# PCB_-_BOARD.net
KiCad netlist of a schematic drawn in EAGLE
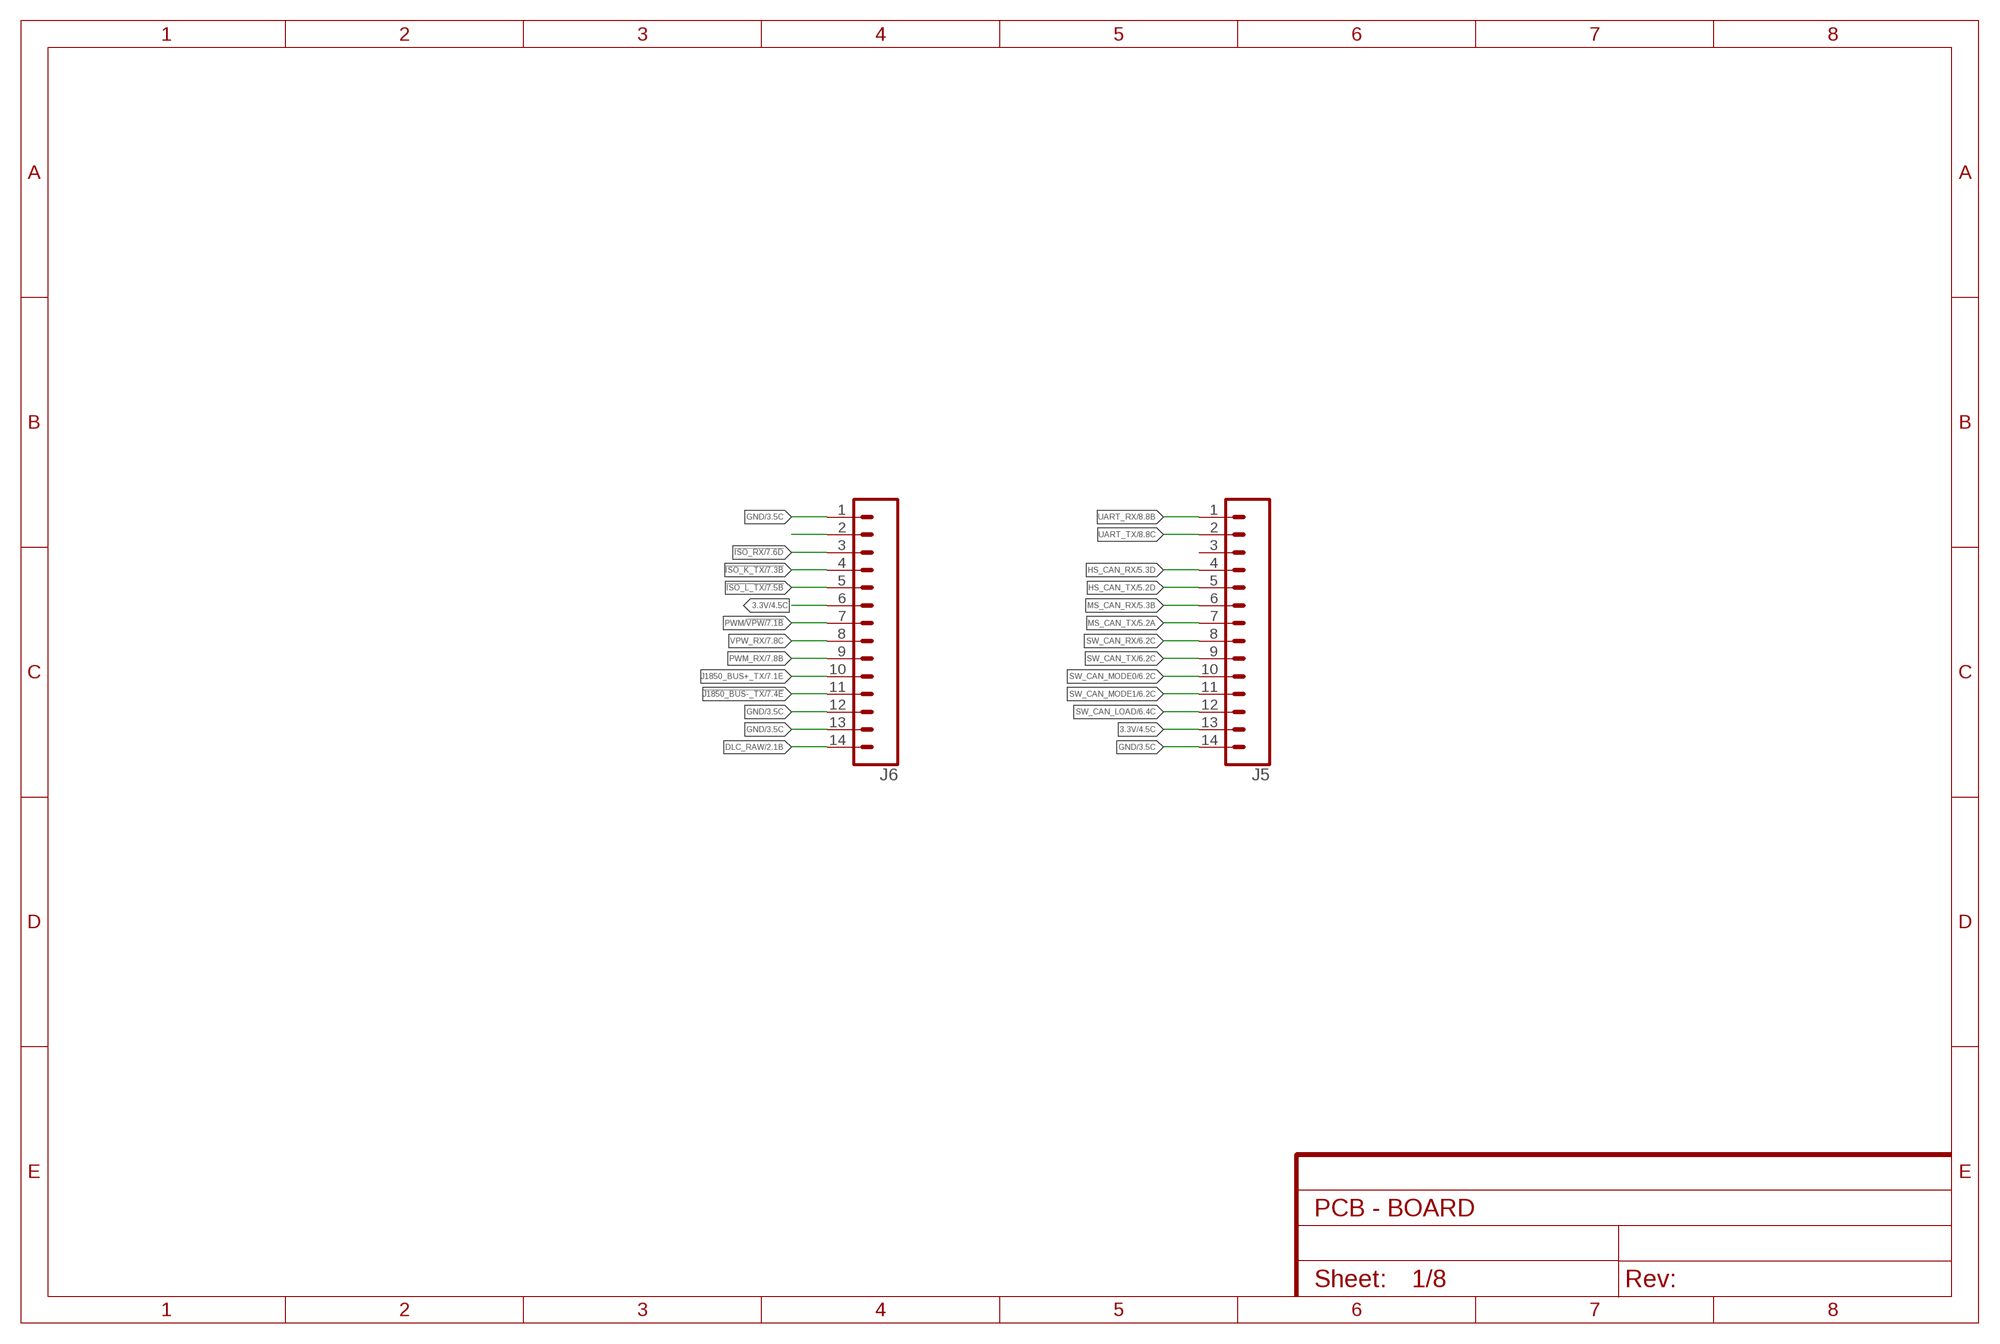
[diagram p0: schematic, sheet 1]
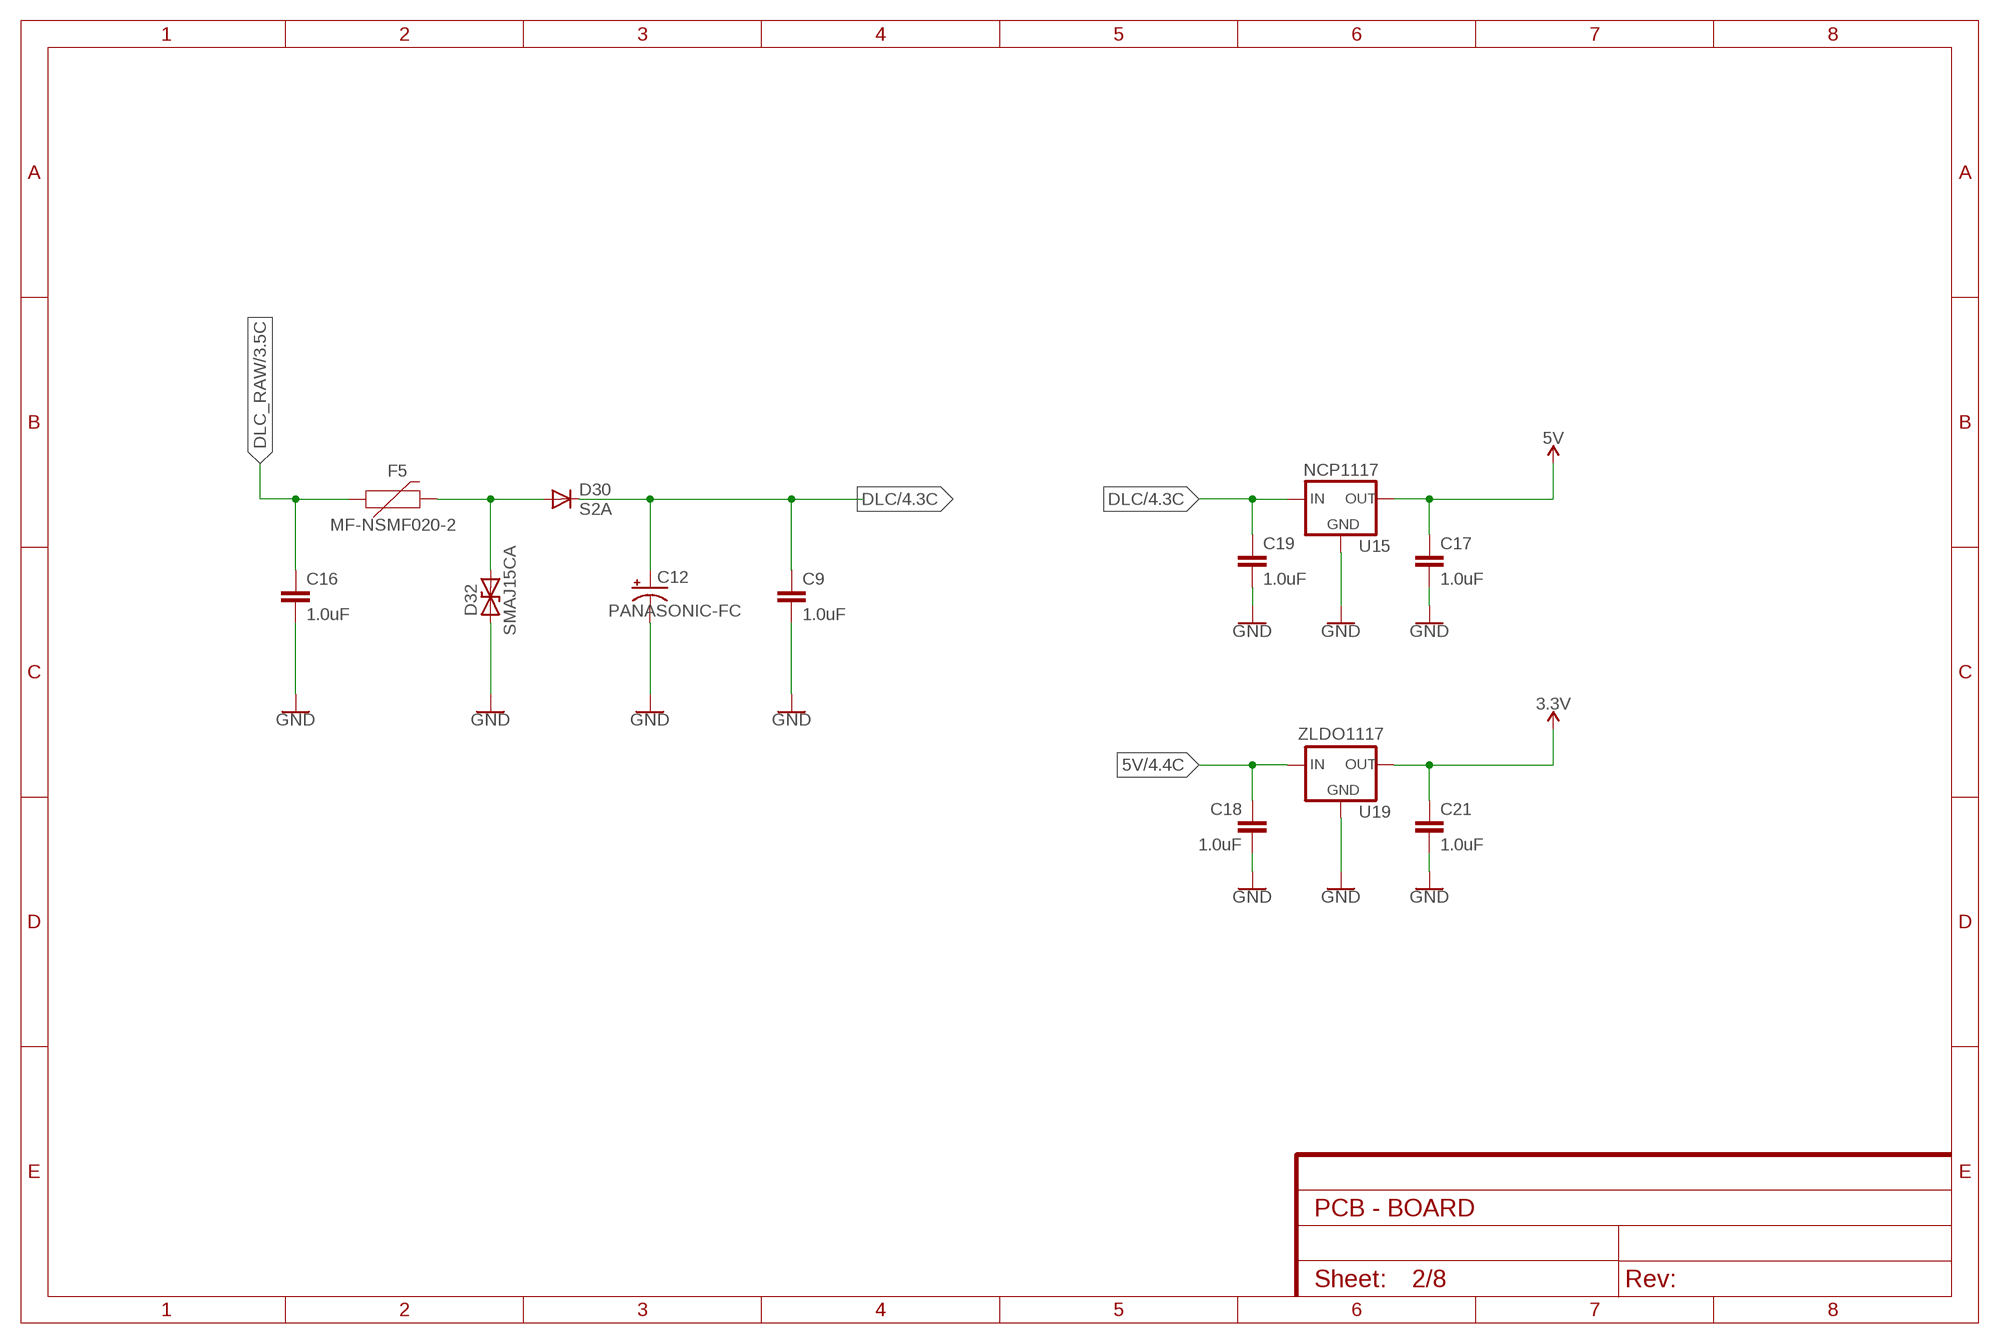
[diagram p1: schematic, sheet 2]
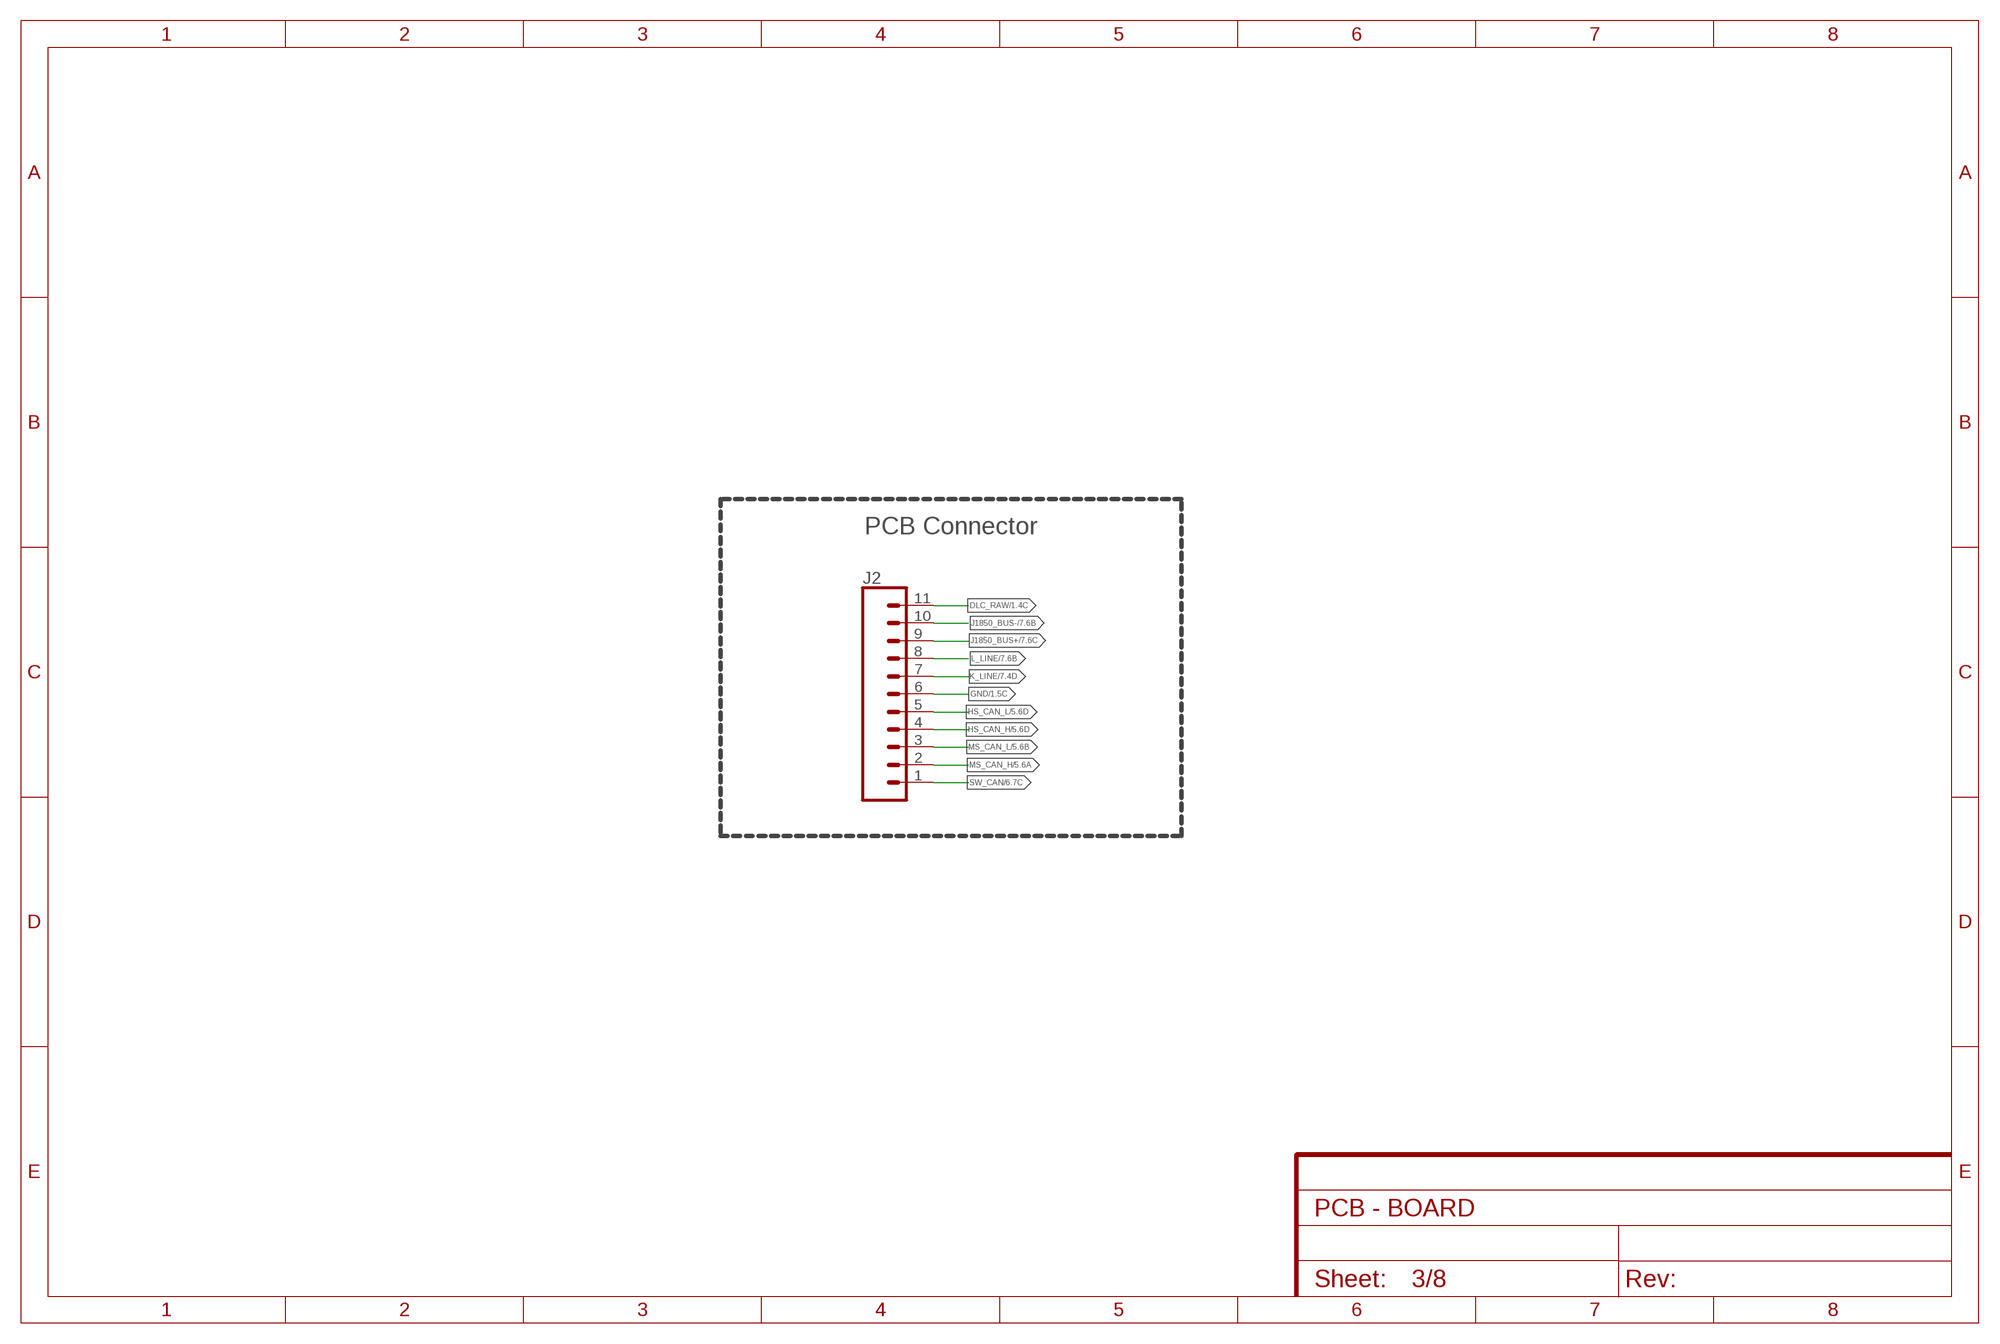
[diagram p2: schematic, sheet 3]
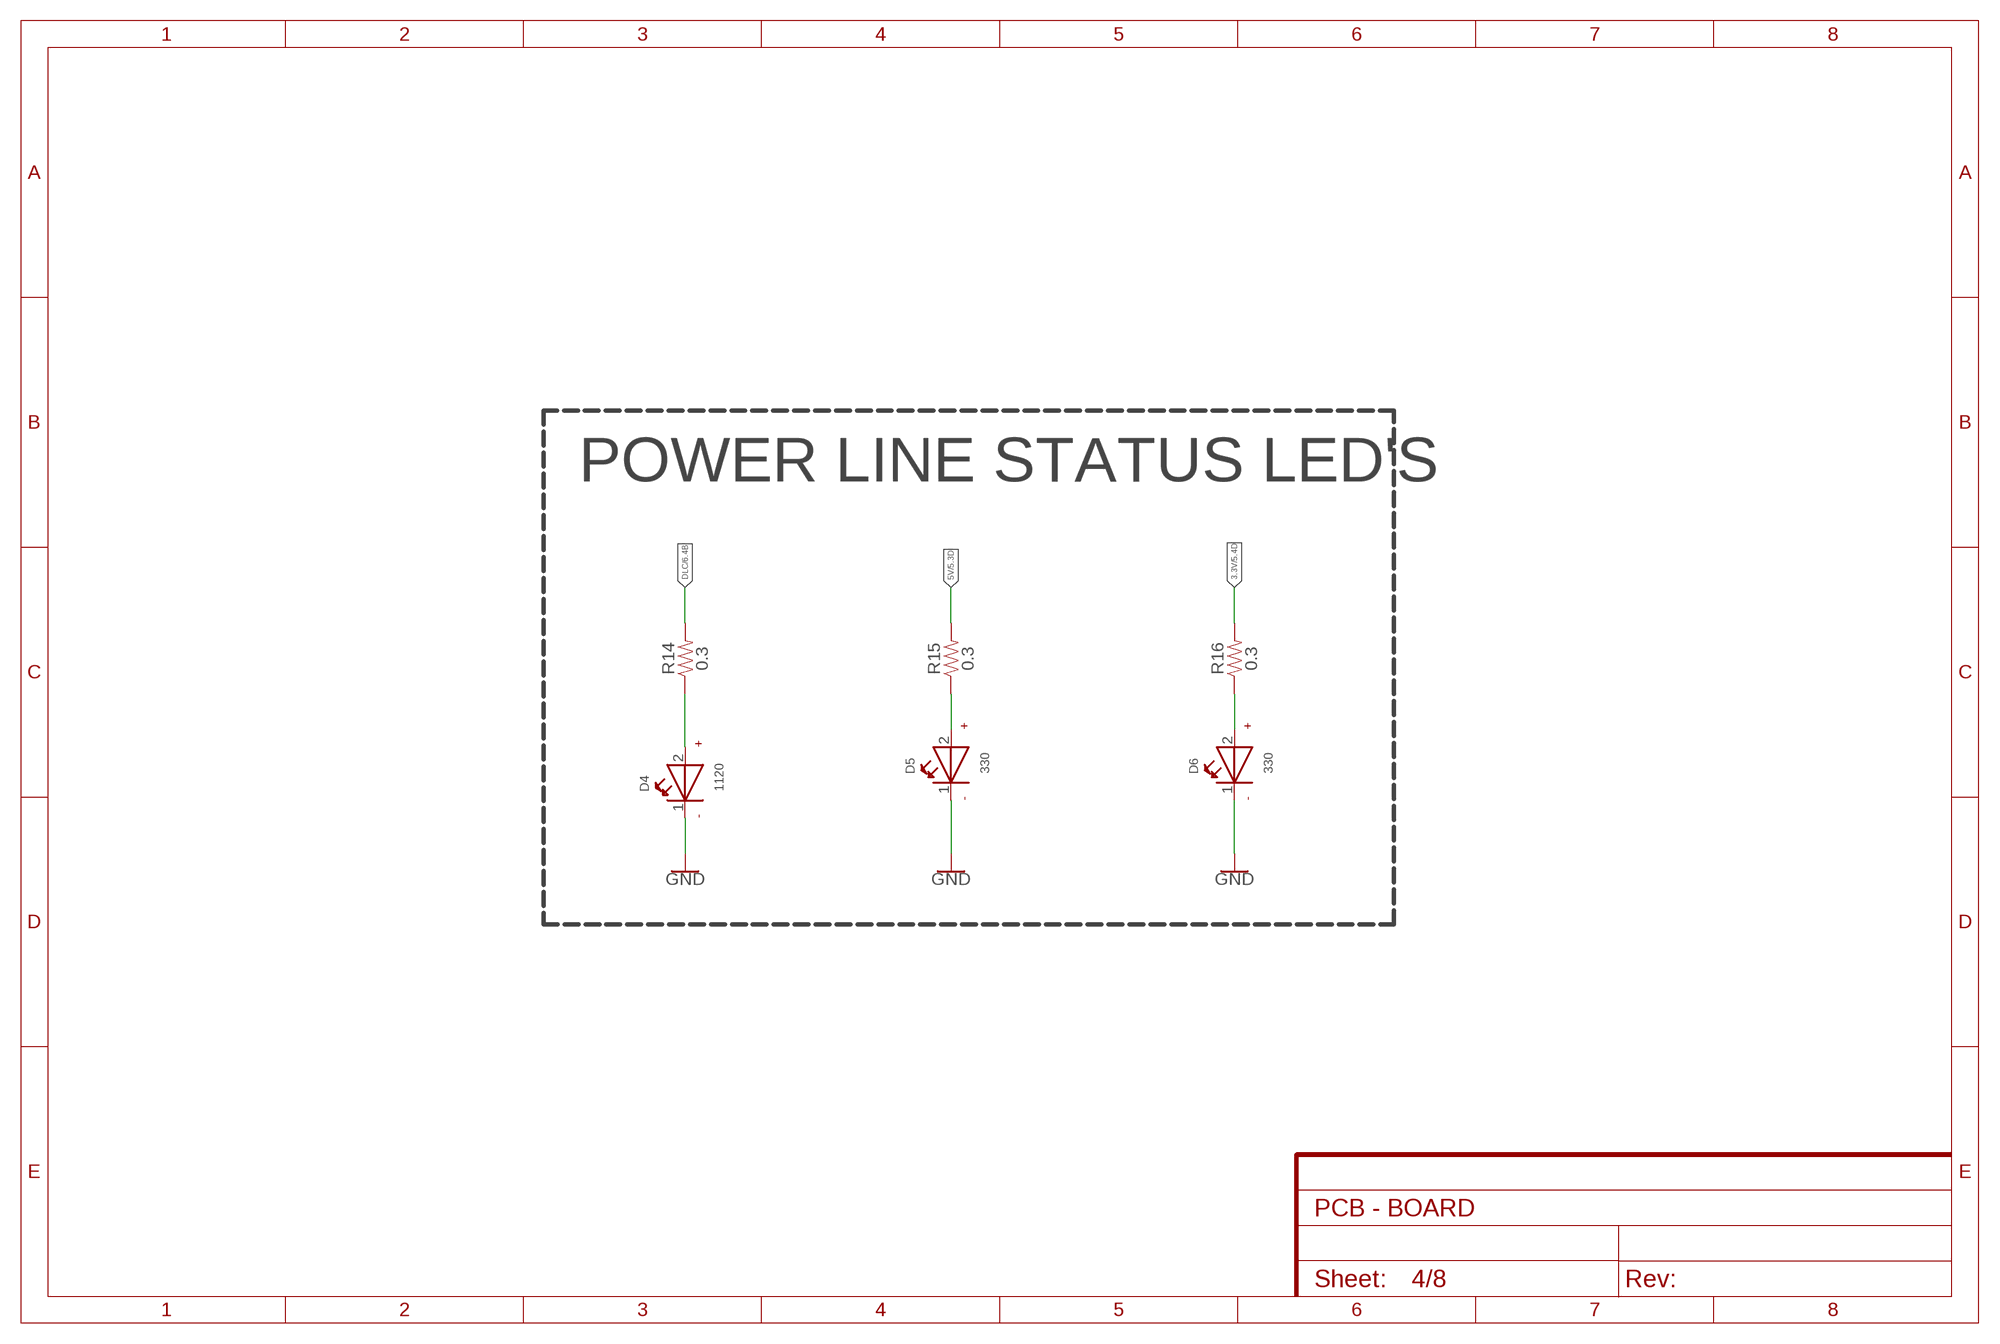
[diagram p3: schematic, sheet 4]
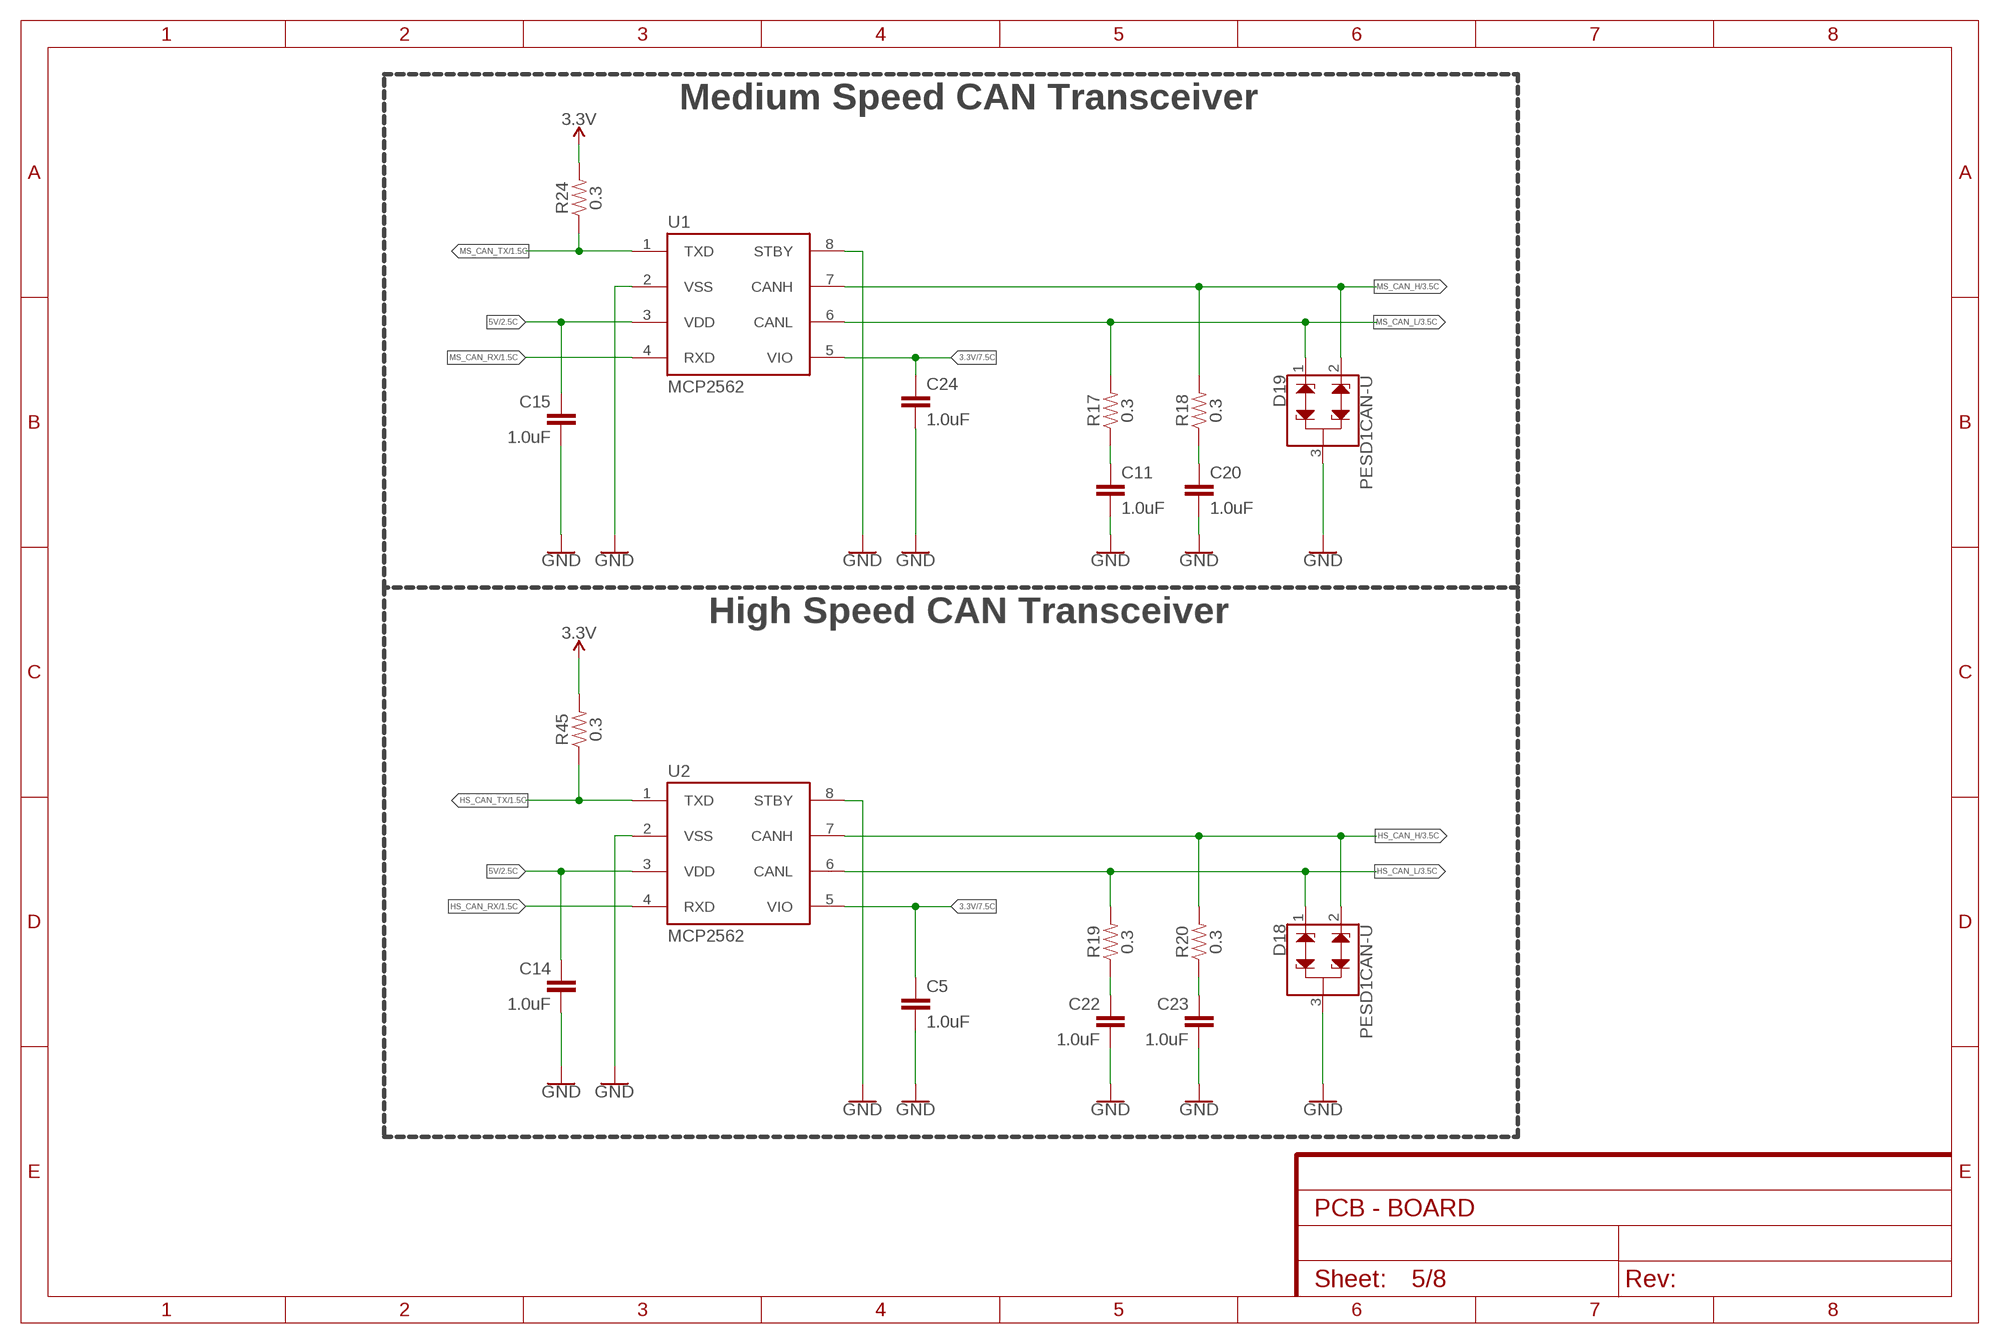
[diagram p4: schematic, sheet 5]
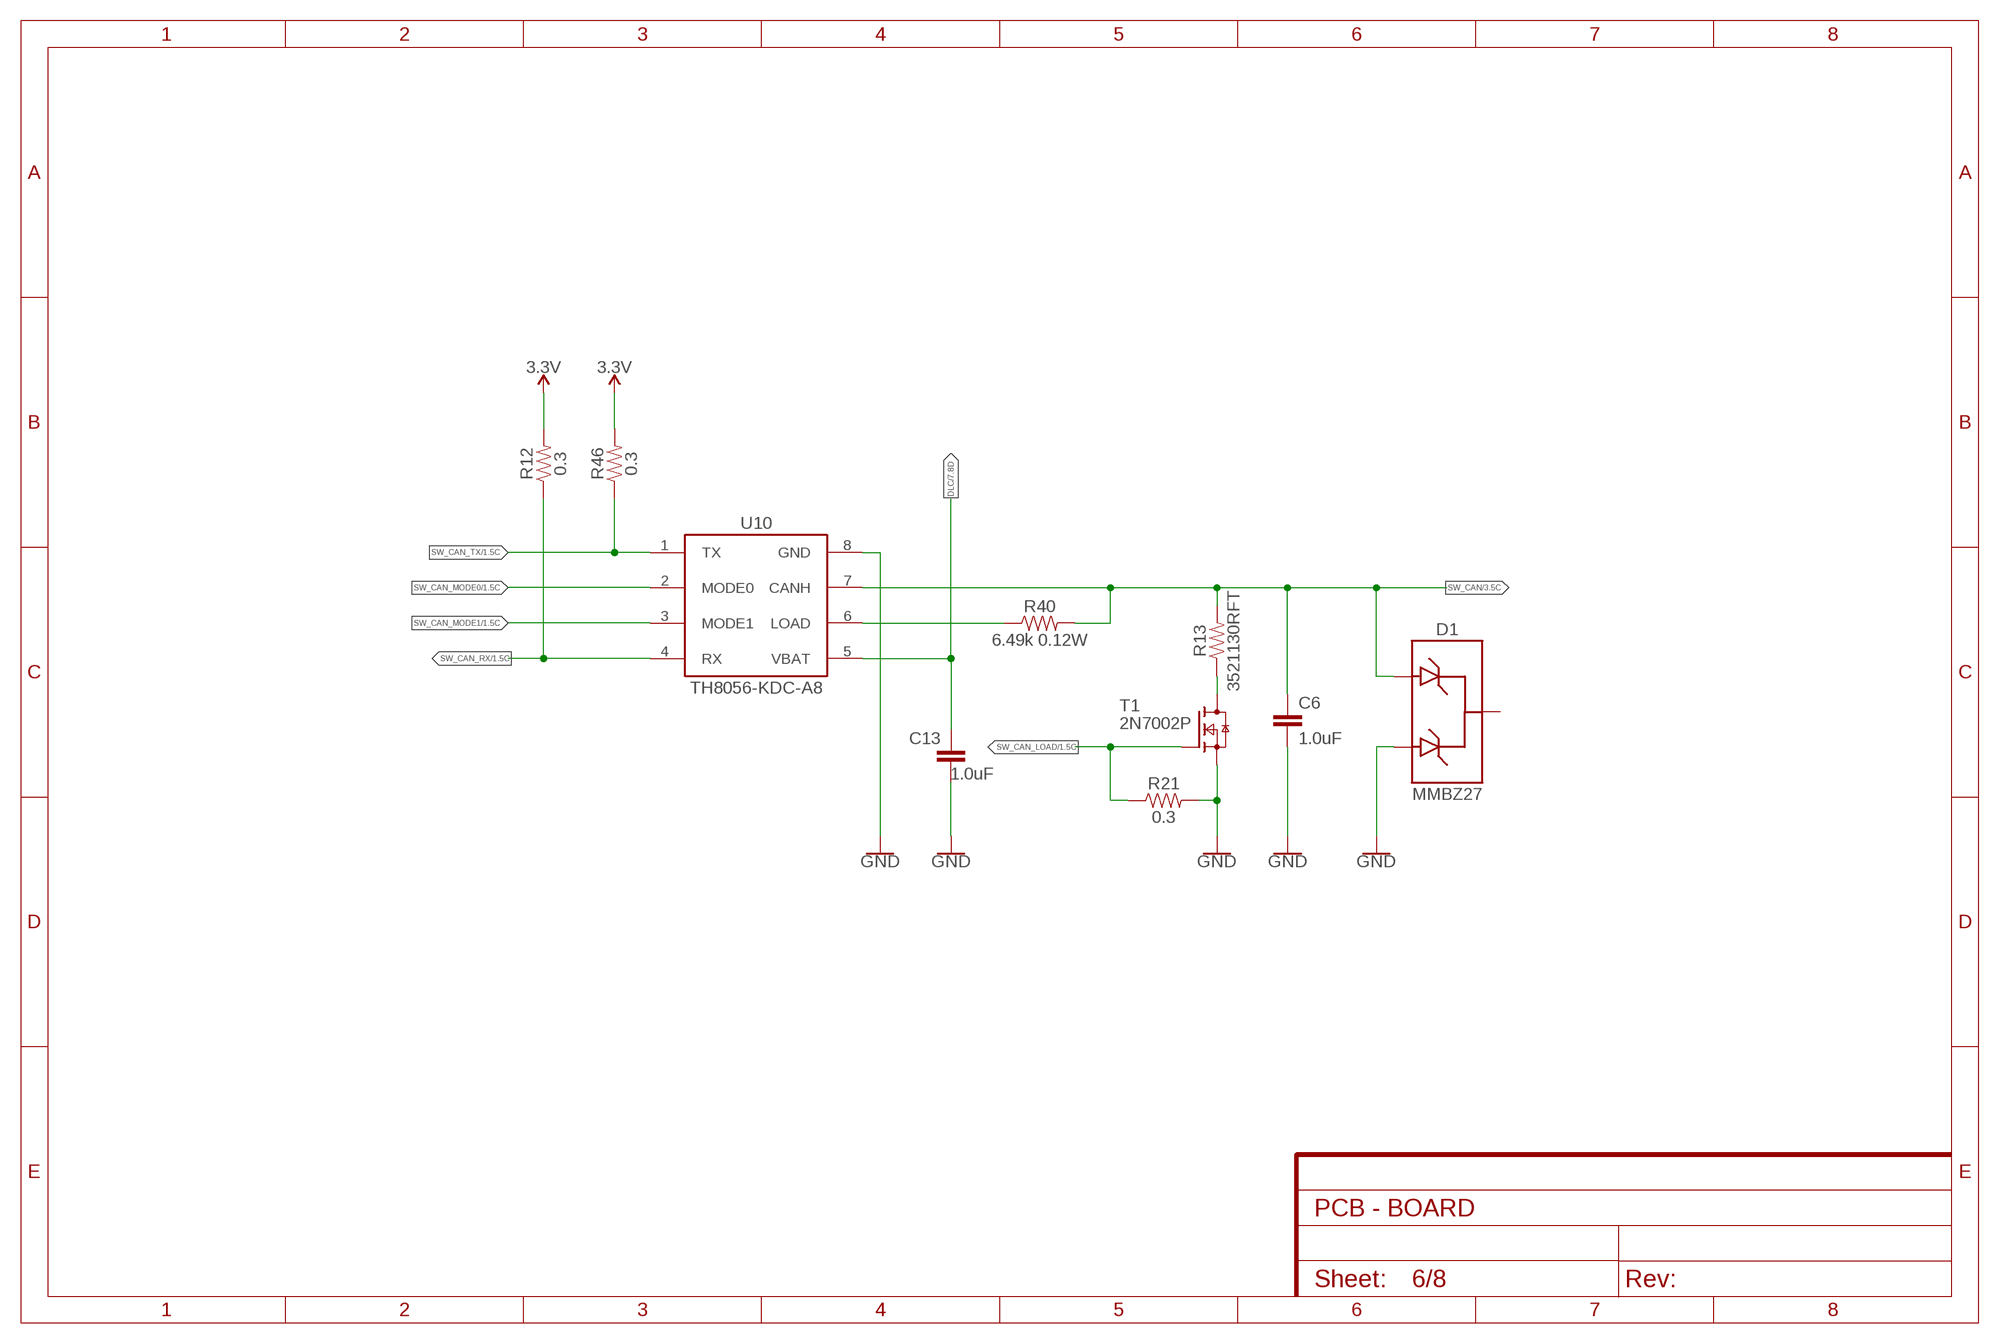
[diagram p5: schematic, sheet 6]
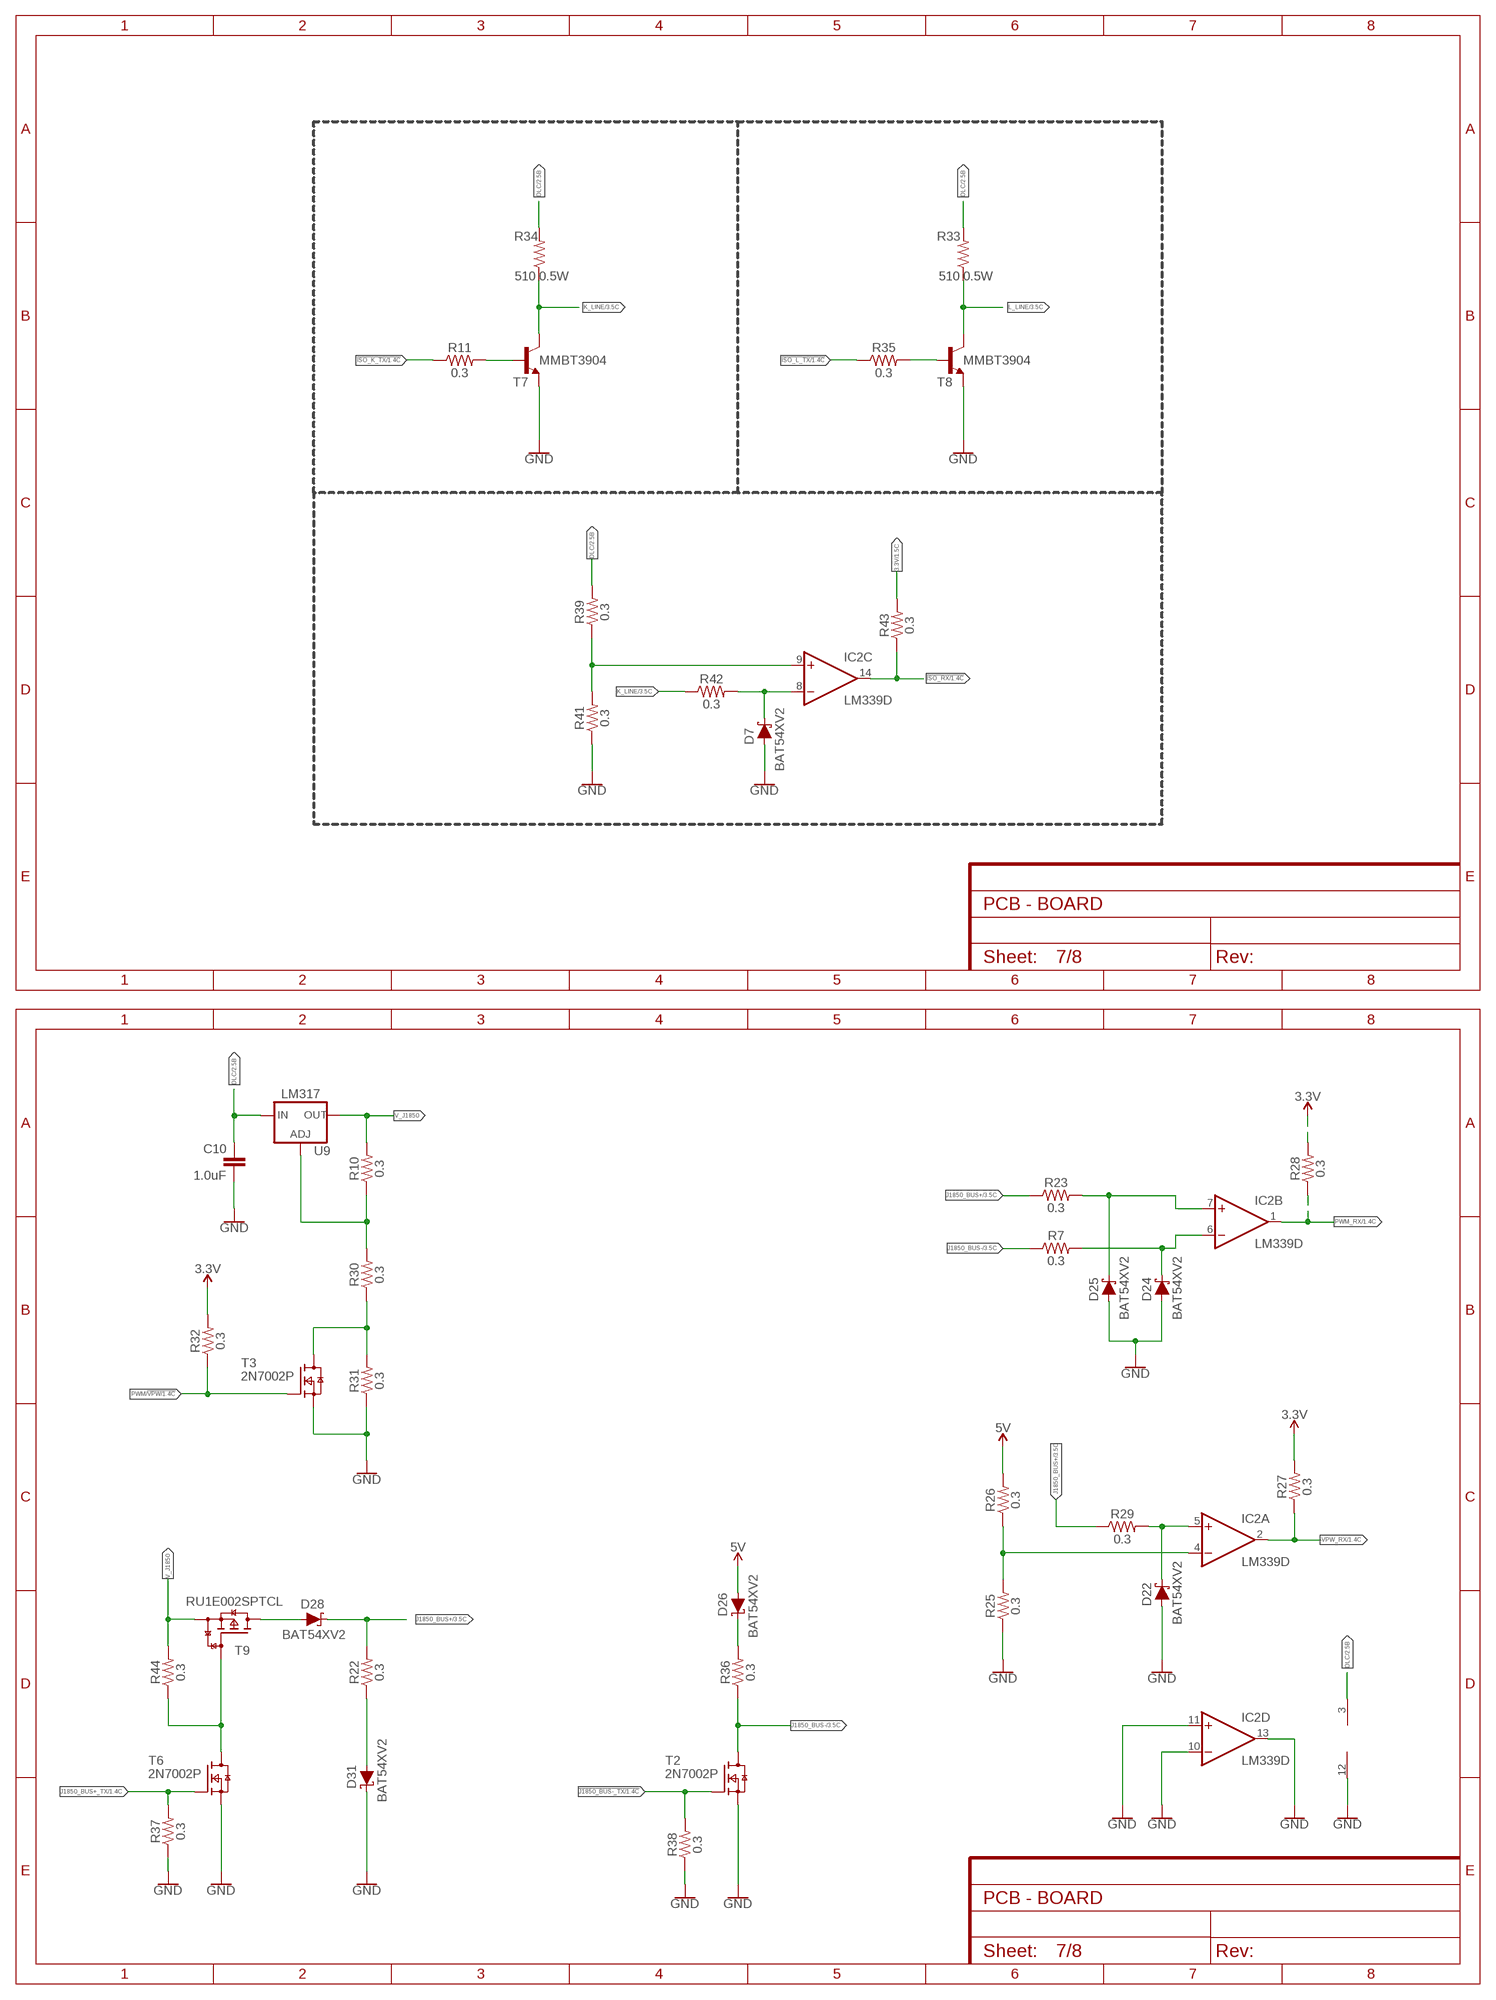
[diagram p6: schematic, sheet 7]
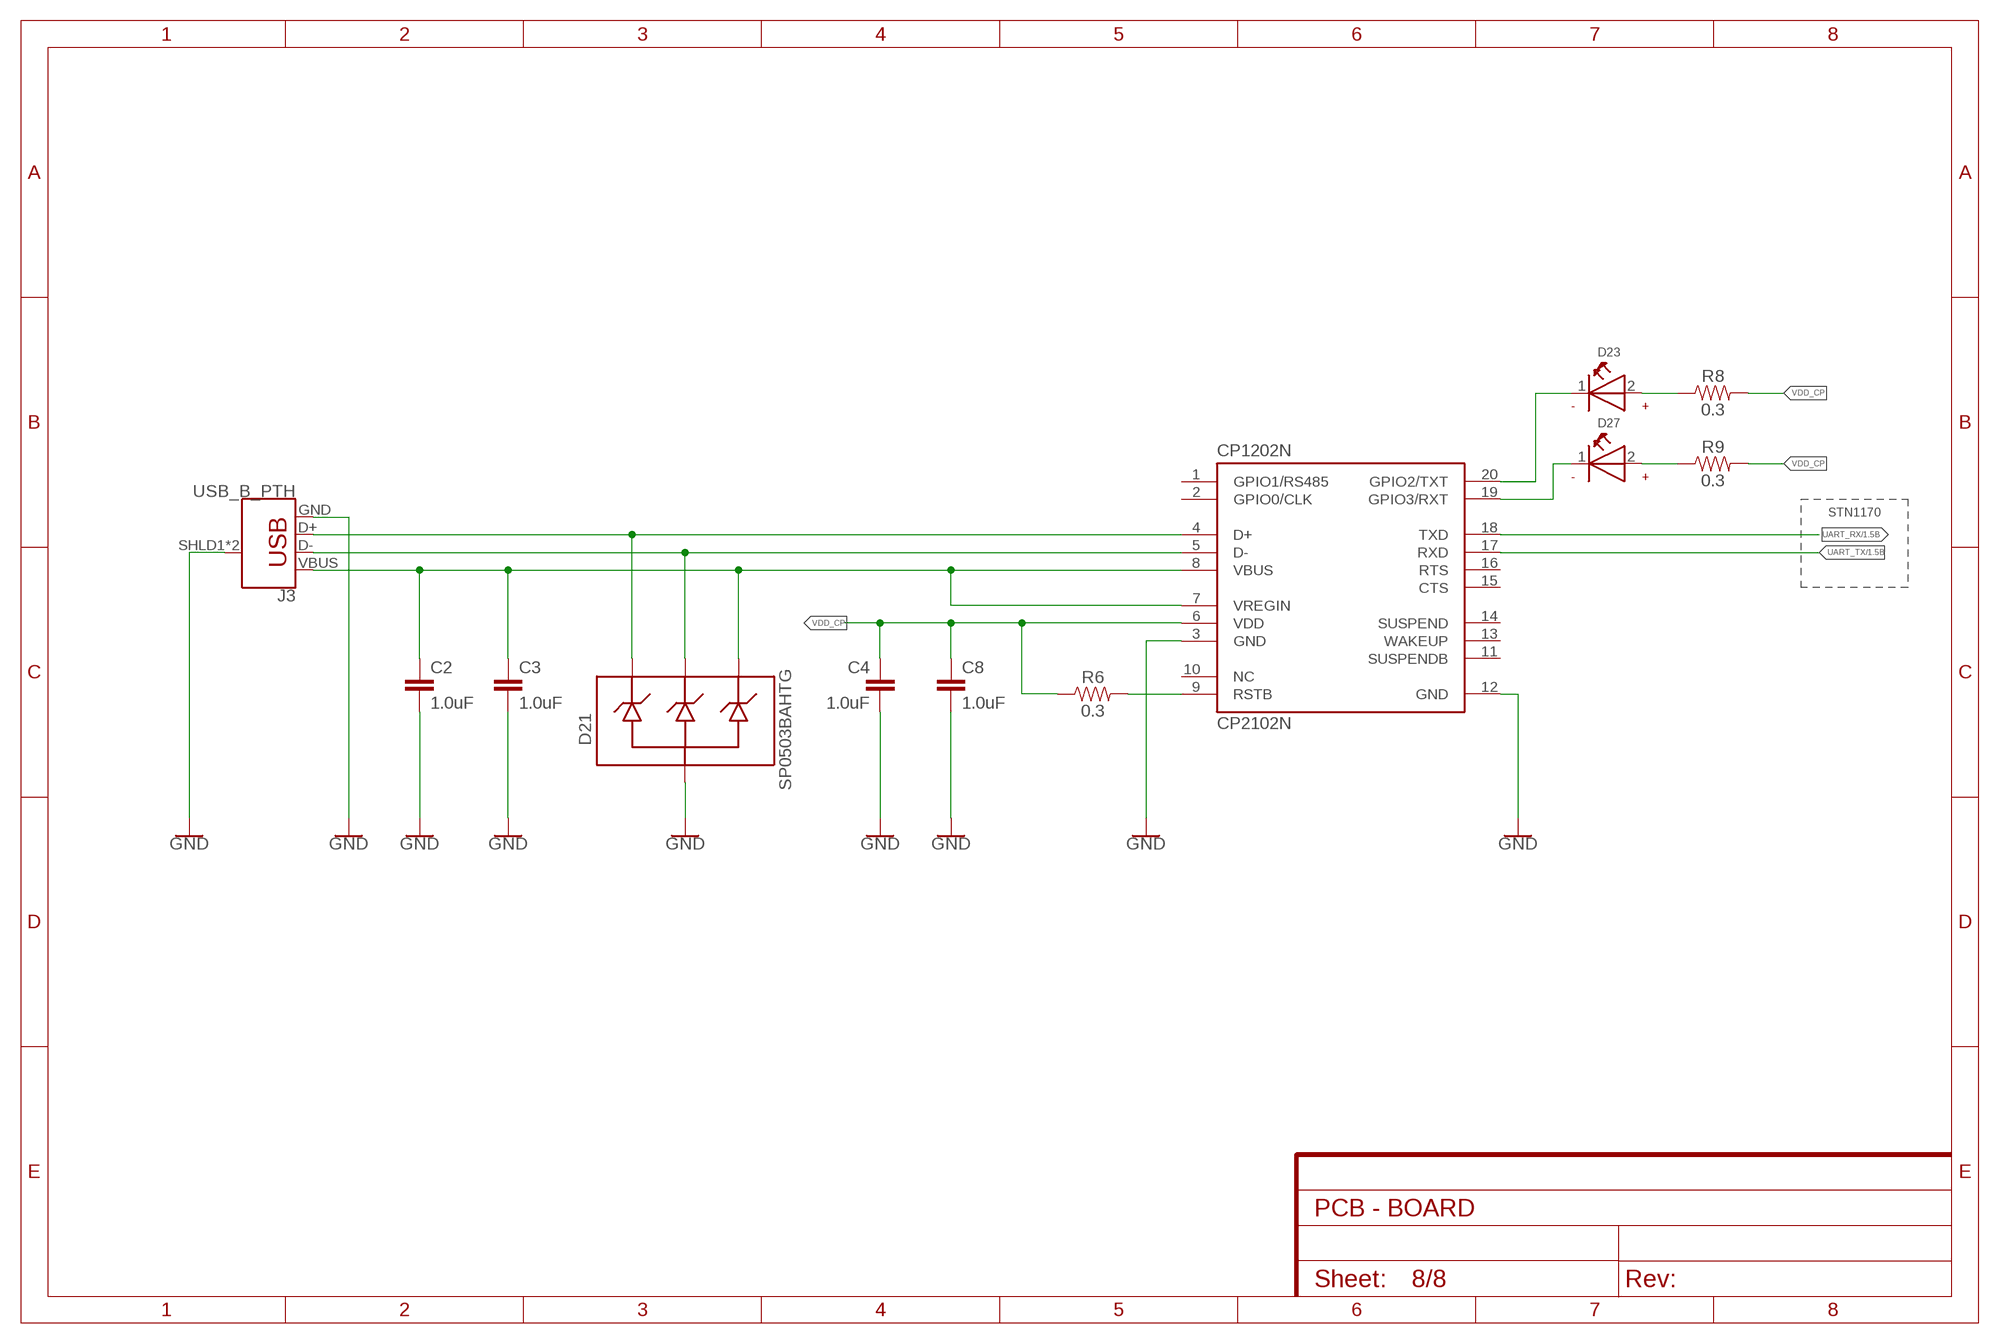
[diagram p7: schematic, sheet 8]

(export (version "E")
  (design (tool "Eeschema 10.0.6"))
  (components
    (comp (ref "C6")
      (value "1.0uF")
      (footprint "eagle-import:0805")
      (libsource (lib "eagle-import") (part "1.0UF-0805-25V-(+80/-20%)"))
    )
    (comp (ref "C13")
      (value "1.0uF")
      (footprint "eagle-import:0805")
      (libsource (lib "eagle-import") (part "1.0UF-0805-25V-(+80/-20%)"))
    )
    (comp (ref "D1")
      (value "MMBZ27")
      (footprint "eagle-import:SOT23-3")
      (libsource (lib "eagle-import") (part "MMBZ27"))
    )
    (comp (ref "R12")
      (value "0.3")
      (footprint "eagle-import:0805")
      (libsource (lib "eagle-import") (part "0.3OHM-0805-1/8W-1%"))
    )
    (comp (ref "R13")
      (value "3521130RFT")
      (footprint "eagle-import:3521")
      (libsource (lib "eagle-import") (part "3521130RFT"))
    )
    (comp (ref "R21")
      (value "0.3")
      (footprint "eagle-import:0805")
      (libsource (lib "eagle-import") (part "0.3OHM-0805-1/8W-1%"))
    )
    (comp (ref "R40")
      (value "6.49k 0.12W")
      (footprint "eagle-import:1206")
      (libsource (lib "eagle-import") (part "10OHM-1206-1/4W-1%"))
    )
    (comp (ref "R46")
      (value "0.3")
      (footprint "eagle-import:0805")
      (libsource (lib "eagle-import") (part "0.3OHM-0805-1/8W-1%"))
    )
    (comp (ref "T1")
      (value "2N7002P")
      (footprint "eagle-import:SOT23")
      (libsource (lib "eagle-import") (part "2N7002P"))
    )
    (comp (ref "U10")
      (value "TH8056-KDC-A8")
      (footprint "eagle-import:SOIC-8")
      (libsource (lib "eagle-import") (part "TH8056-KDC-A8"))
    )
    (comp (ref "J5")
      (value "CONN_14")
      (footprint "eagle-import:1X14")
      (libsource (lib "eagle-import") (part "CONN_14"))
    )
    (comp (ref "J6")
      (value "CONN_14")
      (footprint "eagle-import:1X14")
      (libsource (lib "eagle-import") (part "CONN_14"))
    )
    (comp (ref "D4")
      (value "1120")
      (footprint "eagle-import:WL-SMCW_1206")
      (libsource (lib "eagle-import") (part "WL-SMCW-150120BS75000-B"))
    )
    (comp (ref "D5")
      (value "330")
      (footprint "eagle-import:WL-SMCW_1206")
      (libsource (lib "eagle-import") (part "WL-SMCW-150120BS75000-B"))
    )
    (comp (ref "D6")
      (value "330")
      (footprint "eagle-import:WL-SMCW_1206")
      (libsource (lib "eagle-import") (part "WL-SMCW-150120BS75000-B"))
    )
    (comp (ref "R14")
      (value "0.3")
      (footprint "eagle-import:0805")
      (libsource (lib "eagle-import") (part "0.3OHM-0805-1/8W-1%"))
    )
    (comp (ref "R15")
      (value "0.3")
      (footprint "eagle-import:0805")
      (libsource (lib "eagle-import") (part "0.3OHM-0805-1/8W-1%"))
    )
    (comp (ref "R16")
      (value "0.3")
      (footprint "eagle-import:0805")
      (libsource (lib "eagle-import") (part "0.3OHM-0805-1/8W-1%"))
    )
    (comp (ref "C10")
      (value "1.0uF")
      (footprint "eagle-import:0805")
      (libsource (lib "eagle-import") (part "1.0UF-0805-25V-(+80/-20%)"))
    )
    (comp (ref "D7")
      (value "BAT54XV2")
      (footprint "eagle-import:SOD-523F")
      (libsource (lib "eagle-import") (part "BAT54XV2"))
    )
    (comp (ref "D22")
      (value "BAT54XV2")
      (footprint "eagle-import:SOD-523F")
      (libsource (lib "eagle-import") (part "BAT54XV2"))
    )
    (comp (ref "D24")
      (value "BAT54XV2")
      (footprint "eagle-import:SOD-523F")
      (libsource (lib "eagle-import") (part "BAT54XV2"))
    )
    (comp (ref "D25")
      (value "BAT54XV2")
      (footprint "eagle-import:SOD-523F")
      (libsource (lib "eagle-import") (part "BAT54XV2"))
    )
    (comp (ref "D26")
      (value "BAT54XV2")
      (footprint "eagle-import:SOD-523F")
      (libsource (lib "eagle-import") (part "BAT54XV2"))
    )
    (comp (ref "D28")
      (value "BAT54XV2")
      (footprint "eagle-import:SOD-523F")
      (libsource (lib "eagle-import") (part "BAT54XV2"))
    )
    (comp (ref "D31")
      (value "BAT54XV2")
      (footprint "eagle-import:SOD-523F")
      (libsource (lib "eagle-import") (part "BAT54XV2"))
    )
    (comp (ref "IC2")
      (value "LM339D")
      (footprint "eagle-import:SO14")
      (libsource (lib "eagle-import") (part "LM339D"))
    )
    (comp (ref "R7")
      (value "0.3")
      (footprint "eagle-import:0805")
      (libsource (lib "eagle-import") (part "0.3OHM-0805-1/8W-1%"))
    )
    (comp (ref "R10")
      (value "0.3")
      (footprint "eagle-import:0805")
      (libsource (lib "eagle-import") (part "0.3OHM-0805-1/8W-1%"))
    )
    (comp (ref "R11")
      (value "0.3")
      (footprint "eagle-import:0805")
      (libsource (lib "eagle-import") (part "0.3OHM-0805-1/8W-1%"))
    )
    (comp (ref "R22")
      (value "0.3")
      (footprint "eagle-import:0805")
      (libsource (lib "eagle-import") (part "0.3OHM-0805-1/8W-1%"))
    )
    (comp (ref "R23")
      (value "0.3")
      (footprint "eagle-import:0805")
      (libsource (lib "eagle-import") (part "0.3OHM-0805-1/8W-1%"))
    )
    (comp (ref "R25")
      (value "0.3")
      (footprint "eagle-import:0805")
      (libsource (lib "eagle-import") (part "0.3OHM-0805-1/8W-1%"))
    )
    (comp (ref "R26")
      (value "0.3")
      (footprint "eagle-import:0805")
      (libsource (lib "eagle-import") (part "0.3OHM-0805-1/8W-1%"))
    )
    (comp (ref "R27")
      (value "0.3")
      (footprint "eagle-import:0805")
      (libsource (lib "eagle-import") (part "0.3OHM-0805-1/8W-1%"))
    )
    (comp (ref "R28")
      (value "0.3")
      (footprint "eagle-import:0805")
      (libsource (lib "eagle-import") (part "0.3OHM-0805-1/8W-1%"))
    )
    (comp (ref "R29")
      (value "0.3")
      (footprint "eagle-import:0805")
      (libsource (lib "eagle-import") (part "0.3OHM-0805-1/8W-1%"))
    )
    (comp (ref "R30")
      (value "0.3")
      (footprint "eagle-import:0805")
      (libsource (lib "eagle-import") (part "0.3OHM-0805-1/8W-1%"))
    )
    (comp (ref "R31")
      (value "0.3")
      (footprint "eagle-import:0805")
      (libsource (lib "eagle-import") (part "0.3OHM-0805-1/8W-1%"))
    )
    (comp (ref "R32")
      (value "0.3")
      (footprint "eagle-import:0805")
      (libsource (lib "eagle-import") (part "0.3OHM-0805-1/8W-1%"))
    )
    (comp (ref "R33")
      (value "510 0.5W")
      (footprint "eagle-import:1210")
      (libsource (lib "eagle-import") (part "0.1OHM-1210-1/2W-1%"))
    )
    (comp (ref "R34")
      (value "510 0.5W")
      (footprint "eagle-import:1210")
      (libsource (lib "eagle-import") (part "0.1OHM-1210-1/2W-1%"))
    )
    (comp (ref "R35")
      (value "0.3")
      (footprint "eagle-import:0805")
      (libsource (lib "eagle-import") (part "0.3OHM-0805-1/8W-1%"))
    )
    (comp (ref "R36")
      (value "0.3")
      (footprint "eagle-import:0805")
      (libsource (lib "eagle-import") (part "0.3OHM-0805-1/8W-1%"))
    )
    (comp (ref "R37")
      (value "0.3")
      (footprint "eagle-import:0805")
      (libsource (lib "eagle-import") (part "0.3OHM-0805-1/8W-1%"))
    )
    (comp (ref "R38")
      (value "0.3")
      (footprint "eagle-import:0805")
      (libsource (lib "eagle-import") (part "0.3OHM-0805-1/8W-1%"))
    )
    (comp (ref "R39")
      (value "0.3")
      (footprint "eagle-import:0805")
      (libsource (lib "eagle-import") (part "0.3OHM-0805-1/8W-1%"))
    )
    (comp (ref "R41")
      (value "0.3")
      (footprint "eagle-import:0805")
      (libsource (lib "eagle-import") (part "0.3OHM-0805-1/8W-1%"))
    )
    (comp (ref "R42")
      (value "0.3")
      (footprint "eagle-import:0805")
      (libsource (lib "eagle-import") (part "0.3OHM-0805-1/8W-1%"))
    )
    (comp (ref "R43")
      (value "0.3")
      (footprint "eagle-import:0805")
      (libsource (lib "eagle-import") (part "0.3OHM-0805-1/8W-1%"))
    )
    (comp (ref "R44")
      (value "0.3")
      (footprint "eagle-import:0805")
      (libsource (lib "eagle-import") (part "0.3OHM-0805-1/8W-1%"))
    )
    (comp (ref "T2")
      (value "2N7002P")
      (footprint "eagle-import:SOT23")
      (libsource (lib "eagle-import") (part "2N7002P"))
    )
    (comp (ref "T3")
      (value "2N7002P")
      (footprint "eagle-import:SOT23")
      (libsource (lib "eagle-import") (part "2N7002P"))
    )
    (comp (ref "T6")
      (value "2N7002P")
      (footprint "eagle-import:SOT23")
      (libsource (lib "eagle-import") (part "2N7002P"))
    )
    (comp (ref "T7")
      (value "MMBT3904")
      (footprint "eagle-import:SOT23-BEC")
      (libsource (lib "eagle-import") (part "-NPN-SOT23-BECMMBT3904LT1"))
    )
    (comp (ref "T8")
      (value "MMBT3904")
      (footprint "eagle-import:SOT23-BEC")
      (libsource (lib "eagle-import") (part "-NPN-SOT23-BECMMBT3904LT1"))
    )
    (comp (ref "T9")
      (value "RU1E002SPTCL")
      (footprint "eagle-import:SOT323")
      (libsource (lib "eagle-import") (part "BSS84AKW"))
    )
    (comp (ref "U9")
      (value "LM317")
      (footprint "eagle-import:SOT223")
      (libsource (lib "eagle-import") (part "V_REG_317SMD"))
    )
    (comp (ref "C9")
      (value "1.0uF")
      (footprint "eagle-import:0805")
      (libsource (lib "eagle-import") (part "1.0UF-0805-25V-(+80/-20%)"))
    )
    (comp (ref "C12")
      (value "PANASONIC-FC")
      (footprint "eagle-import:5X11")
      (libsource (lib "eagle-import") (part "PANASONIC-FC"))
    )
    (comp (ref "C16")
      (value "1.0uF")
      (footprint "eagle-import:0805")
      (libsource (lib "eagle-import") (part "1.0UF-0805-25V-(+80/-20%)"))
    )
    (comp (ref "C17")
      (value "1.0uF")
      (footprint "eagle-import:0805")
      (libsource (lib "eagle-import") (part "1.0UF-0805-25V-(+80/-20%)"))
    )
    (comp (ref "C18")
      (value "1.0uF")
      (footprint "eagle-import:0805")
      (libsource (lib "eagle-import") (part "1.0UF-0805-25V-(+80/-20%)"))
    )
    (comp (ref "C19")
      (value "1.0uF")
      (footprint "eagle-import:0805")
      (libsource (lib "eagle-import") (part "1.0UF-0805-25V-(+80/-20%)"))
    )
    (comp (ref "C21")
      (value "1.0uF")
      (footprint "eagle-import:0805")
      (libsource (lib "eagle-import") (part "1.0UF-0805-25V-(+80/-20%)"))
    )
    (comp (ref "D30")
      (value "S2A")
      (footprint "eagle-import:DO214AA")
      (fields (field (name "MF") "Fairchild"))
      (libsource (lib "eagle-import") (part "S2A"))
    )
    (comp (ref "D32")
      (value "SMAJ15CA")
      (footprint "eagle-import:DO214AC")
      (fields (field (name "MF") "Littelfuse"))
      (libsource (lib "eagle-import") (part "SMAJCA15"))
    )
    (comp (ref "F5")
      (value "MF-NSMF020-2")
      (footprint "eagle-import:1206")
      (libsource (lib "eagle-import") (part "PPTC_THREE-QUARTER-AMP"))
    )
    (comp (ref "U15")
      (value "NCP1117")
      (footprint "eagle-import:TO-252")
      (libsource (lib "eagle-import") (part "NCP1117DPAK"))
    )
    (comp (ref "U19")
      (value "ZLDO1117")
      (footprint "eagle-import:SOT223")
      (libsource (lib "eagle-import") (part "ZLDO1117SOT223"))
    )
    (comp (ref "C5")
      (value "1.0uF")
      (footprint "eagle-import:0805")
      (libsource (lib "eagle-import") (part "1.0UF-0805-25V-(+80/-20%)"))
    )
    (comp (ref "C11")
      (value "1.0uF")
      (footprint "eagle-import:0805")
      (libsource (lib "eagle-import") (part "1.0UF-0805-25V-(+80/-20%)"))
    )
    (comp (ref "C14")
      (value "1.0uF")
      (footprint "eagle-import:0805")
      (libsource (lib "eagle-import") (part "1.0UF-0805-25V-(+80/-20%)"))
    )
    (comp (ref "C15")
      (value "1.0uF")
      (footprint "eagle-import:0805")
      (libsource (lib "eagle-import") (part "1.0UF-0805-25V-(+80/-20%)"))
    )
    (comp (ref "C20")
      (value "1.0uF")
      (footprint "eagle-import:0805")
      (libsource (lib "eagle-import") (part "1.0UF-0805-25V-(+80/-20%)"))
    )
    (comp (ref "C22")
      (value "1.0uF")
      (footprint "eagle-import:0805")
      (libsource (lib "eagle-import") (part "1.0UF-0805-25V-(+80/-20%)"))
    )
    (comp (ref "C23")
      (value "1.0uF")
      (footprint "eagle-import:0805")
      (libsource (lib "eagle-import") (part "1.0UF-0805-25V-(+80/-20%)"))
    )
    (comp (ref "C24")
      (value "1.0uF")
      (footprint "eagle-import:0805")
      (libsource (lib "eagle-import") (part "1.0UF-0805-25V-(+80/-20%)"))
    )
    (comp (ref "D18")
      (value "PESD1CAN-U")
      (footprint "eagle-import:SOT323")
      (libsource (lib "eagle-import") (part "PESD1CAN-U"))
    )
    (comp (ref "D19")
      (value "PESD1CAN-U")
      (footprint "eagle-import:SOT323")
      (libsource (lib "eagle-import") (part "PESD1CAN-U"))
    )
    (comp (ref "R17")
      (value "0.3")
      (footprint "eagle-import:0805")
      (libsource (lib "eagle-import") (part "0.3OHM-0805-1/8W-1%"))
    )
    (comp (ref "R18")
      (value "0.3")
      (footprint "eagle-import:0805")
      (libsource (lib "eagle-import") (part "0.3OHM-0805-1/8W-1%"))
    )
    (comp (ref "R19")
      (value "0.3")
      (footprint "eagle-import:0805")
      (libsource (lib "eagle-import") (part "0.3OHM-0805-1/8W-1%"))
    )
    (comp (ref "R20")
      (value "0.3")
      (footprint "eagle-import:0805")
      (libsource (lib "eagle-import") (part "0.3OHM-0805-1/8W-1%"))
    )
    (comp (ref "R24")
      (value "0.3")
      (footprint "eagle-import:0805")
      (libsource (lib "eagle-import") (part "0.3OHM-0805-1/8W-1%"))
    )
    (comp (ref "R45")
      (value "0.3")
      (footprint "eagle-import:0805")
      (libsource (lib "eagle-import") (part "0.3OHM-0805-1/8W-1%"))
    )
    (comp (ref "U1")
      (value "MCP2562")
      (footprint "eagle-import:SOIC-8")
      (libsource (lib "eagle-import") (part "MCP2562"))
    )
    (comp (ref "U2")
      (value "MCP2562")
      (footprint "eagle-import:SOIC-8")
      (libsource (lib "eagle-import") (part "MCP2562"))
    )
    (comp (ref "J2")
      (value "CONN_11")
      (footprint "eagle-import:1X11")
      (libsource (lib "eagle-import") (part "CONN_11"))
    )
    (comp (ref "C2")
      (value "1.0uF")
      (footprint "eagle-import:0805")
      (libsource (lib "eagle-import") (part "1.0UF-0805-25V-(+80/-20%)"))
    )
    (comp (ref "C3")
      (value "1.0uF")
      (footprint "eagle-import:0805")
      (libsource (lib "eagle-import") (part "1.0UF-0805-25V-(+80/-20%)"))
    )
    (comp (ref "C4")
      (value "1.0uF")
      (footprint "eagle-import:0805")
      (libsource (lib "eagle-import") (part "1.0UF-0805-25V-(+80/-20%)"))
    )
    (comp (ref "C8")
      (value "1.0uF")
      (footprint "eagle-import:0805")
      (libsource (lib "eagle-import") (part "1.0UF-0805-25V-(+80/-20%)"))
    )
    (comp (ref "CP1202N")
      (value "CP2102N")
      (footprint "eagle-import:QFN20")
      (libsource (lib "eagle-import") (part "CP2102N"))
    )
    (comp (ref "D21")
      (value "SP0503BAHTG")
      (footprint "eagle-import:SOT143-4")
      (libsource (lib "eagle-import") (part "SP0503BAHTG"))
    )
    (comp (ref "D23")
      (value "WL-SMCW-150120BS75000-B")
      (footprint "eagle-import:WL-SMCW_1206")
      (libsource (lib "eagle-import") (part "WL-SMCW-150120BS75000-B"))
    )
    (comp (ref "D27")
      (value "WL-SMCW-150120BS75000-B")
      (footprint "eagle-import:WL-SMCW_1206")
      (libsource (lib "eagle-import") (part "WL-SMCW-150120BS75000-B"))
    )
    (comp (ref "J3")
      (value "USB_B_PTH")
      (footprint "eagle-import:USB-B-PTH")
      (libsource (lib "eagle-import") (part "USB_B_PTH"))
    )
    (comp (ref "R6")
      (value "0.3")
      (footprint "eagle-import:0805")
      (libsource (lib "eagle-import") (part "0.3OHM-0805-1/8W-1%"))
    )
    (comp (ref "R8")
      (value "0.3")
      (footprint "eagle-import:0805")
      (libsource (lib "eagle-import") (part "0.3OHM-0805-1/8W-1%"))
    )
    (comp (ref "R9")
      (value "0.3")
      (footprint "eagle-import:0805")
      (libsource (lib "eagle-import") (part "0.3OHM-0805-1/8W-1%"))
    )
  )
  (nets
    (net (code "1") (name "3.3V") (class "Default")
      (node (ref "C21") (pin "1") (pinfunction "1_1") (pintype "passive"))
      (node (ref "C24") (pin "1") (pinfunction "1_1") (pintype "passive"))
      (node (ref "C5") (pin "1") (pinfunction "1_1") (pintype "passive"))
      (node (ref "J5") (pin "13") (pinfunction "13_13") (pintype "passive"))
      (node (ref "J6") (pin "6") (pinfunction "6_6") (pintype "passive"))
      (node (ref "R12") (pin "2") (pinfunction "2_2") (pintype "passive"))
      (node (ref "R16") (pin "2") (pinfunction "2_2") (pintype "passive"))
      (node (ref "R24") (pin "2") (pinfunction "2_2") (pintype "passive"))
      (node (ref "R27") (pin "2") (pinfunction "2_2") (pintype "passive"))
      (node (ref "R28") (pin "2") (pinfunction "2_2") (pintype "passive"))
      (node (ref "R32") (pin "2") (pinfunction "2_2") (pintype "passive"))
      (node (ref "R43") (pin "2") (pinfunction "2_2") (pintype "passive"))
      (node (ref "R45") (pin "2") (pinfunction "2_2") (pintype "passive"))
      (node (ref "R46") (pin "2") (pinfunction "2_2") (pintype "passive"))
      (node (ref "U1") (pin "5") (pinfunction "VIO_5") (pintype "bidirectional"))
      (node (ref "U19") (pin "2") (pinfunction "OUT_2") (pintype "passive"))
      (node (ref "U19") (pin "4") (pinfunction "OUT_4") (pintype "passive"))
      (node (ref "U2") (pin "5") (pinfunction "VIO_5") (pintype "bidirectional"))
    )
    (net (code "2") (name "5V") (class "Default")
      (node (ref "C14") (pin "1") (pinfunction "1_1") (pintype "passive"))
      (node (ref "C15") (pin "1") (pinfunction "1_1") (pintype "passive"))
      (node (ref "C17") (pin "1") (pinfunction "1_1") (pintype "passive"))
      (node (ref "C18") (pin "1") (pinfunction "1_1") (pintype "passive"))
      (node (ref "D26") (pin "A") (pinfunction "A_A") (pintype "passive"))
      (node (ref "R15") (pin "2") (pinfunction "2_2") (pintype "passive"))
      (node (ref "R26") (pin "2") (pinfunction "2_2") (pintype "passive"))
      (node (ref "U1") (pin "3") (pinfunction "VDD_3") (pintype "bidirectional"))
      (node (ref "U15") (pin "2") (pinfunction "OUT_2") (pintype "passive"))
      (node (ref "U19") (pin "3") (pinfunction "IN_3") (pintype "input"))
      (node (ref "U2") (pin "3") (pinfunction "VDD_3") (pintype "bidirectional"))
    )
    (net (code "3") (name "DLC") (class "Default")
      (node (ref "C10") (pin "1") (pinfunction "1_1") (pintype "passive"))
      (node (ref "C12") (pin "2") (pinfunction "+_2") (pintype "passive"))
      (node (ref "C13") (pin "1") (pinfunction "1_1") (pintype "passive"))
      (node (ref "C19") (pin "1") (pinfunction "1_1") (pintype "passive"))
      (node (ref "C9") (pin "1") (pinfunction "1_1") (pintype "passive"))
      (node (ref "D30") (pin "C") (pinfunction "C_C") (pintype "passive"))
      (node (ref "IC2") (pin "3") (pinfunction "V+_3") (pintype "power_in"))
      (node (ref "R14") (pin "2") (pinfunction "2_2") (pintype "passive"))
      (node (ref "R33") (pin "2") (pinfunction "2_2") (pintype "passive"))
      (node (ref "R34") (pin "2") (pinfunction "2_2") (pintype "passive"))
      (node (ref "R39") (pin "2") (pinfunction "2_2") (pintype "passive"))
      (node (ref "U10") (pin "5") (pinfunction "VBAT_5") (pintype "power_in"))
      (node (ref "U15") (pin "3") (pinfunction "IN_3") (pintype "input"))
      (node (ref "U9") (pin "3") (pinfunction "IN_3") (pintype "input"))
    )
    (net (code "4") (name "DLC_RAW") (class "Default")
      (node (ref "C16") (pin "1") (pinfunction "1_1") (pintype "passive"))
      (node (ref "F5") (pin "1") (pinfunction "1_1") (pintype "bidirectional"))
      (node (ref "J2") (pin "11") (pinfunction "11_11") (pintype "passive"))
      (node (ref "J6") (pin "14") (pinfunction "14_14") (pintype "passive"))
    )
    (net (code "5") (name "GND") (class "Default")
      (node (ref "C10") (pin "2") (pinfunction "2_2") (pintype "passive"))
      (node (ref "C11") (pin "2") (pinfunction "2_2") (pintype "passive"))
      (node (ref "C12") (pin "1") (pinfunction "-_1") (pintype "passive"))
      (node (ref "C13") (pin "2") (pinfunction "2_2") (pintype "passive"))
      (node (ref "C14") (pin "2") (pinfunction "2_2") (pintype "passive"))
      (node (ref "C15") (pin "2") (pinfunction "2_2") (pintype "passive"))
      (node (ref "C16") (pin "2") (pinfunction "2_2") (pintype "passive"))
      (node (ref "C17") (pin "2") (pinfunction "2_2") (pintype "passive"))
      (node (ref "C18") (pin "2") (pinfunction "2_2") (pintype "passive"))
      (node (ref "C19") (pin "2") (pinfunction "2_2") (pintype "passive"))
      (node (ref "C2") (pin "2") (pinfunction "2_2") (pintype "passive"))
      (node (ref "C20") (pin "2") (pinfunction "2_2") (pintype "passive"))
      (node (ref "C21") (pin "2") (pinfunction "2_2") (pintype "passive"))
      (node (ref "C22") (pin "2") (pinfunction "2_2") (pintype "passive"))
      (node (ref "C23") (pin "2") (pinfunction "2_2") (pintype "passive"))
      (node (ref "C24") (pin "2") (pinfunction "2_2") (pintype "passive"))
      (node (ref "C3") (pin "2") (pinfunction "2_2") (pintype "passive"))
      (node (ref "C4") (pin "2") (pinfunction "2_2") (pintype "passive"))
      (node (ref "C5") (pin "2") (pinfunction "2_2") (pintype "passive"))
      (node (ref "C6") (pin "2") (pinfunction "2_2") (pintype "passive"))
      (node (ref "C8") (pin "2") (pinfunction "2_2") (pintype "passive"))
      (node (ref "C9") (pin "2") (pinfunction "2_2") (pintype "passive"))
      (node (ref "CP1202N") (pin "12") (pinfunction "GND_12") (pintype "power_in"))
      (node (ref "CP1202N") (pin "3") (pinfunction "GND_3") (pintype "power_in"))
      (node (ref "D1") (pin "2") (pinfunction "A2_2") (pintype "passive"))
      (node (ref "D18") (pin "3") (pinfunction "3_3") (pintype "bidirectional"))
      (node (ref "D19") (pin "3") (pinfunction "3_3") (pintype "bidirectional"))
      (node (ref "D21") (pin "1") (pinfunction "1_1") (pintype "passive"))
      (node (ref "D22") (pin "A") (pinfunction "A_A") (pintype "passive"))
      (node (ref "D24") (pin "A") (pinfunction "A_A") (pintype "passive"))
      (node (ref "D25") (pin "A") (pinfunction "A_A") (pintype "passive"))
      (node (ref "D31") (pin "C") (pinfunction "C_C") (pintype "passive"))
      (node (ref "D32") (pin "A") (pinfunction "1_A") (pintype "passive"))
      (node (ref "D4") (pin "1") (pinfunction "-_1") (pintype "passive"))
      (node (ref "D5") (pin "1") (pinfunction "-_1") (pintype "passive"))
      (node (ref "D6") (pin "1") (pinfunction "-_1") (pintype "passive"))
      (node (ref "D7") (pin "A") (pinfunction "A_A") (pintype "passive"))
      (node (ref "IC2") (pin "10") (pinfunction "-IN_10") (pintype "input"))
      (node (ref "IC2") (pin "11") (pinfunction "+IN_11") (pintype "input"))
      (node (ref "IC2") (pin "12") (pinfunction "GND_12") (pintype "power_in"))
      (node (ref "IC2") (pin "13") (pinfunction "OUT_13") (pintype "open_collector"))
      (node (ref "J2") (pin "6") (pinfunction "6_6") (pintype "passive"))
      (node (ref "J3") (pin "GND") (pinfunction "GND_GND") (pintype "power_in"))
      (node (ref "J3") (pin "SHLD1") (pinfunction "SHIELD_SHLD1") (pintype "bidirectional"))
      (node (ref "J3") (pin "SHLD2") (pinfunction "SHIELD_SHLD2") (pintype "bidirectional"))
      (node (ref "J5") (pin "14") (pinfunction "14_14") (pintype "passive"))
      (node (ref "J6") (pin "1") (pinfunction "1_1") (pintype "passive"))
      (node (ref "J6") (pin "12") (pinfunction "12_12") (pintype "passive"))
      (node (ref "J6") (pin "13") (pinfunction "13_13") (pintype "passive"))
      (node (ref "J6") (pin "2") (pinfunction "2_2") (pintype "passive"))
      (node (ref "R21") (pin "2") (pinfunction "2_2") (pintype "passive"))
      (node (ref "R25") (pin "1") (pinfunction "1_1") (pintype "passive"))
      (node (ref "R31") (pin "1") (pinfunction "1_1") (pintype "passive"))
      (node (ref "R37") (pin "1") (pinfunction "1_1") (pintype "passive"))
      (node (ref "R38") (pin "1") (pinfunction "1_1") (pintype "passive"))
      (node (ref "R41") (pin "1") (pinfunction "1_1") (pintype "passive"))
      (node (ref "T1") (pin "2") (pinfunction "S_2") (pintype "passive"))
      (node (ref "T2") (pin "2") (pinfunction "S_2") (pintype "passive"))
      (node (ref "T3") (pin "2") (pinfunction "S_2") (pintype "passive"))
      (node (ref "T6") (pin "2") (pinfunction "S_2") (pintype "passive"))
      (node (ref "T7") (pin "E") (pinfunction "E_E") (pintype "passive"))
      (node (ref "T8") (pin "E") (pinfunction "E_E") (pintype "passive"))
      (node (ref "U1") (pin "2") (pinfunction "VSS_2") (pintype "bidirectional"))
      (node (ref "U1") (pin "8") (pinfunction "STBY_8") (pintype "bidirectional"))
      (node (ref "U10") (pin "8") (pinfunction "GND_8") (pintype "power_in"))
      (node (ref "U15") (pin "1") (pinfunction "GND_1") (pintype "input"))
      (node (ref "U19") (pin "1") (pinfunction "GND_1") (pintype "input"))
      (node (ref "U2") (pin "2") (pinfunction "VSS_2") (pintype "bidirectional"))
      (node (ref "U2") (pin "8") (pinfunction "STBY_8") (pintype "bidirectional"))
    )
    (net (code "6") (name "HS_CAN_H") (class "Default")
      (node (ref "D18") (pin "2") (pinfunction "2_2") (pintype "bidirectional"))
      (node (ref "J2") (pin "4") (pinfunction "4_4") (pintype "passive"))
      (node (ref "R20") (pin "2") (pinfunction "2_2") (pintype "passive"))
      (node (ref "U2") (pin "7") (pinfunction "CANH_7") (pintype "bidirectional"))
    )
    (net (code "7") (name "HS_CAN_L") (class "Default")
      (node (ref "D18") (pin "1") (pinfunction "1_1") (pintype "bidirectional"))
      (node (ref "J2") (pin "5") (pinfunction "5_5") (pintype "passive"))
      (node (ref "R19") (pin "2") (pinfunction "2_2") (pintype "passive"))
      (node (ref "U2") (pin "6") (pinfunction "CANL_6") (pintype "bidirectional"))
    )
    (net (code "8") (name "HS_CAN_RX") (class "Default")
      (node (ref "J5") (pin "4") (pinfunction "4_4") (pintype "passive"))
      (node (ref "U2") (pin "4") (pinfunction "RXD_4") (pintype "bidirectional"))
    )
    (net (code "9") (name "HS_CAN_TX") (class "Default")
      (node (ref "J5") (pin "5") (pinfunction "5_5") (pintype "passive"))
      (node (ref "R45") (pin "1") (pinfunction "1_1") (pintype "passive"))
      (node (ref "U2") (pin "1") (pinfunction "TXD_1") (pintype "bidirectional"))
    )
    (net (code "10") (name "J1850_BUS+") (class "Default")
      (node (ref "D25") (pin "C") (pinfunction "C_C") (pintype "passive"))
      (node (ref "D28") (pin "C") (pinfunction "C_C") (pintype "passive"))
      (node (ref "IC2") (pin "7") (pinfunction "+IN_7") (pintype "input"))
      (node (ref "J2") (pin "9") (pinfunction "9_9") (pintype "passive"))
      (node (ref "R22") (pin "2") (pinfunction "2_2") (pintype "passive"))
      (node (ref "R23") (pin "1") (pinfunction "1_1") (pintype "passive"))
      (node (ref "R23") (pin "2") (pinfunction "2_2") (pintype "passive"))
      (node (ref "R29") (pin "1") (pinfunction "1_1") (pintype "passive"))
    )
    (net (code "11") (name "J1850_BUS+_TX") (class "Default")
      (node (ref "J6") (pin "10") (pinfunction "10_10") (pintype "passive"))
      (node (ref "R37") (pin "2") (pinfunction "2_2") (pintype "passive"))
      (node (ref "T6") (pin "1") (pinfunction "G_1") (pintype "passive"))
    )
    (net (code "12") (name "J1850_BUS-") (class "Default")
      (node (ref "D24") (pin "C") (pinfunction "C_C") (pintype "passive"))
      (node (ref "IC2") (pin "6") (pinfunction "-IN_6") (pintype "input"))
      (node (ref "J2") (pin "10") (pinfunction "10_10") (pintype "passive"))
      (node (ref "R36") (pin "1") (pinfunction "1_1") (pintype "passive"))
      (node (ref "R7") (pin "1") (pinfunction "1_1") (pintype "passive"))
      (node (ref "R7") (pin "2") (pinfunction "2_2") (pintype "passive"))
      (node (ref "T2") (pin "3") (pinfunction "D_3") (pintype "passive"))
    )
    (net (code "13") (name "K_LINE") (class "Default")
      (node (ref "J2") (pin "7") (pinfunction "7_7") (pintype "passive"))
      (node (ref "R34") (pin "1") (pinfunction "1_1") (pintype "passive"))
      (node (ref "R42") (pin "1") (pinfunction "1_1") (pintype "passive"))
      (node (ref "T7") (pin "C") (pinfunction "C_C") (pintype "passive"))
    )
    (net (code "14") (name "L_LINE") (class "Default")
      (node (ref "J2") (pin "8") (pinfunction "8_8") (pintype "passive"))
      (node (ref "R33") (pin "1") (pinfunction "1_1") (pintype "passive"))
      (node (ref "T8") (pin "C") (pinfunction "C_C") (pintype "passive"))
    )
    (net (code "15") (name "MS_CAN_H") (class "Default")
      (node (ref "D19") (pin "2") (pinfunction "2_2") (pintype "bidirectional"))
      (node (ref "J2") (pin "2") (pinfunction "2_2") (pintype "passive"))
      (node (ref "R18") (pin "2") (pinfunction "2_2") (pintype "passive"))
      (node (ref "U1") (pin "7") (pinfunction "CANH_7") (pintype "bidirectional"))
    )
    (net (code "16") (name "MS_CAN_L") (class "Default")
      (node (ref "D19") (pin "1") (pinfunction "1_1") (pintype "bidirectional"))
      (node (ref "J2") (pin "3") (pinfunction "3_3") (pintype "passive"))
      (node (ref "R17") (pin "2") (pinfunction "2_2") (pintype "passive"))
      (node (ref "U1") (pin "6") (pinfunction "CANL_6") (pintype "bidirectional"))
    )
    (net (code "17") (name "MS_CAN_RX") (class "Default")
      (node (ref "J5") (pin "6") (pinfunction "6_6") (pintype "passive"))
      (node (ref "U1") (pin "4") (pinfunction "RXD_4") (pintype "bidirectional"))
    )
    (net (code "18") (name "MS_CAN_TX") (class "Default")
      (node (ref "J5") (pin "7") (pinfunction "7_7") (pintype "passive"))
      (node (ref "R24") (pin "1") (pinfunction "1_1") (pintype "passive"))
      (node (ref "U1") (pin "1") (pinfunction "TXD_1") (pintype "bidirectional"))
    )
    (net (code "19") (name "Net-(C11-Pad1)") (class "Default")
      (node (ref "C11") (pin "1") (pinfunction "1_1") (pintype "passive"))
      (node (ref "R17") (pin "1") (pinfunction "1_1") (pintype "passive"))
    )
    (net (code "20") (name "Net-(C20-Pad1)") (class "Default")
      (node (ref "C20") (pin "1") (pinfunction "1_1") (pintype "passive"))
      (node (ref "R18") (pin "1") (pinfunction "1_1") (pintype "passive"))
    )
    (net (code "21") (name "Net-(C22-Pad1)") (class "Default")
      (node (ref "C22") (pin "1") (pinfunction "1_1") (pintype "passive"))
      (node (ref "R19") (pin "1") (pinfunction "1_1") (pintype "passive"))
    )
    (net (code "22") (name "Net-(C23-Pad1)") (class "Default")
      (node (ref "C23") (pin "1") (pinfunction "1_1") (pintype "passive"))
      (node (ref "R20") (pin "1") (pinfunction "1_1") (pintype "passive"))
    )
    (net (code "23") (name "Net-(CP1202N-D+)") (class "Default")
      (node (ref "CP1202N") (pin "4") (pinfunction "D+_4") (pintype "input"))
      (node (ref "D21") (pin "4") (pinfunction "4_4") (pintype "passive"))
      (node (ref "J3") (pin "D+") (pinfunction "D+_D+") (pintype "bidirectional"))
    )
    (net (code "24") (name "Net-(CP1202N-D-)") (class "Default")
      (node (ref "CP1202N") (pin "5") (pinfunction "D-_5") (pintype "input"))
      (node (ref "D21") (pin "3") (pinfunction "3_3") (pintype "passive"))
      (node (ref "J3") (pin "D-") (pinfunction "D-_D-") (pintype "bidirectional"))
    )
    (net (code "25") (name "Net-(CP1202N-GPIO2{slash}TXT)") (class "Default")
      (node (ref "CP1202N") (pin "20") (pinfunction "GPIO2/TXT_20") (pintype "bidirectional"))
      (node (ref "D23") (pin "1") (pinfunction "-_1") (pintype "passive"))
    )
    (net (code "26") (name "Net-(CP1202N-GPIO3{slash}RXT)") (class "Default")
      (node (ref "CP1202N") (pin "19") (pinfunction "GPIO3/RXT_19") (pintype "bidirectional"))
      (node (ref "D27") (pin "1") (pinfunction "-_1") (pintype "passive"))
    )
    (net (code "27") (name "Net-(CP1202N-RSTB)") (class "Default")
      (node (ref "CP1202N") (pin "9") (pinfunction "RSTB_9") (pintype "input"))
      (node (ref "R6") (pin "2") (pinfunction "2_2") (pintype "passive"))
    )
    (net (code "28") (name "Net-(CP1202N-VBUS)") (class "Default")
      (node (ref "C2") (pin "1") (pinfunction "1_1") (pintype "passive"))
      (node (ref "C3") (pin "1") (pinfunction "1_1") (pintype "passive"))
      (node (ref "CP1202N") (pin "7") (pinfunction "VREGIN_7") (pintype "power_in"))
      (node (ref "CP1202N") (pin "8") (pinfunction "VBUS_8") (pintype "input"))
      (node (ref "D21") (pin "2") (pinfunction "2_2") (pintype "passive"))
      (node (ref "J3") (pin "VBUS") (pinfunction "VBUS_VBUS") (pintype "power_in"))
    )
    (net (code "29") (name "Net-(D4-+)") (class "Default")
      (node (ref "D4") (pin "2") (pinfunction "+_2") (pintype "passive"))
      (node (ref "R14") (pin "1") (pinfunction "1_1") (pintype "passive"))
    )
    (net (code "30") (name "Net-(D5-+)") (class "Default")
      (node (ref "D5") (pin "2") (pinfunction "+_2") (pintype "passive"))
      (node (ref "R15") (pin "1") (pinfunction "1_1") (pintype "passive"))
    )
    (net (code "31") (name "Net-(D6-+)") (class "Default")
      (node (ref "D6") (pin "2") (pinfunction "+_2") (pintype "passive"))
      (node (ref "R16") (pin "1") (pinfunction "1_1") (pintype "passive"))
    )
    (net (code "32") (name "Net-(D23-+)") (class "Default")
      (node (ref "D23") (pin "2") (pinfunction "+_2") (pintype "passive"))
      (node (ref "R8") (pin "1") (pinfunction "1_1") (pintype "passive"))
    )
    (net (code "33") (name "Net-(D26-PadC)") (class "Default")
      (node (ref "D26") (pin "C") (pinfunction "C_C") (pintype "passive"))
      (node (ref "R36") (pin "2") (pinfunction "2_2") (pintype "passive"))
    )
    (net (code "34") (name "Net-(D27-+)") (class "Default")
      (node (ref "D27") (pin "2") (pinfunction "+_2") (pintype "passive"))
      (node (ref "R9") (pin "1") (pinfunction "1_1") (pintype "passive"))
    )
    (net (code "35") (name "Net-(D31-PadA)") (class "Default")
      (node (ref "D31") (pin "A") (pinfunction "A_A") (pintype "passive"))
      (node (ref "R22") (pin "1") (pinfunction "1_1") (pintype "passive"))
    )
    (net (code "36") (name "Net-(D32-2)") (class "Default")
      (node (ref "D30") (pin "A") (pinfunction "A_A") (pintype "passive"))
      (node (ref "D32") (pin "C") (pinfunction "2_C") (pintype "passive"))
      (node (ref "F5") (pin "2") (pinfunction "2_2") (pintype "bidirectional"))
    )
    (net (code "37") (name "Net-(IC2A-+IN)") (class "Default")
      (node (ref "D22") (pin "C") (pinfunction "C_C") (pintype "passive"))
      (node (ref "IC2") (pin "5") (pinfunction "+IN_5") (pintype "input"))
      (node (ref "R29") (pin "2") (pinfunction "2_2") (pintype "passive"))
    )
    (net (code "38") (name "Net-(IC2A--IN)") (class "Default")
      (node (ref "IC2") (pin "4") (pinfunction "-IN_4") (pintype "input"))
      (node (ref "R25") (pin "2") (pinfunction "2_2") (pintype "passive"))
      (node (ref "R26") (pin "1") (pinfunction "1_1") (pintype "passive"))
    )
    (net (code "39") (name "Net-(IC2C-+IN)") (class "Default")
      (node (ref "IC2") (pin "9") (pinfunction "+IN_9") (pintype "input"))
      (node (ref "R39") (pin "1") (pinfunction "1_1") (pintype "passive"))
      (node (ref "R41") (pin "2") (pinfunction "2_2") (pintype "passive"))
    )
    (net (code "40") (name "Net-(IC2C--IN)") (class "Default")
      (node (ref "D7") (pin "C") (pinfunction "C_C") (pintype "passive"))
      (node (ref "IC2") (pin "8") (pinfunction "-IN_8") (pintype "input"))
      (node (ref "R42") (pin "2") (pinfunction "2_2") (pintype "passive"))
    )
    (net (code "41") (name "Net-(R11-Pad2)") (class "Default")
      (node (ref "R11") (pin "2") (pinfunction "2_2") (pintype "passive"))
      (node (ref "T7") (pin "B") (pinfunction "B_B") (pintype "passive"))
    )
    (net (code "42") (name "Net-(R35-Pad2)") (class "Default")
      (node (ref "R35") (pin "2") (pinfunction "2_2") (pintype "passive"))
      (node (ref "T8") (pin "B") (pinfunction "B_B") (pintype "passive"))
    )
    (net (code "43") (name "Net-(T1-D)") (class "Default")
      (node (ref "R13") (pin "1") (pinfunction "1_1") (pintype "passive"))
      (node (ref "T1") (pin "3") (pinfunction "D_3") (pintype "passive"))
    )
    (net (code "44") (name "Net-(T3-D)") (class "Default")
      (node (ref "R30") (pin "1") (pinfunction "1_1") (pintype "passive"))
      (node (ref "R31") (pin "2") (pinfunction "2_2") (pintype "passive"))
      (node (ref "T3") (pin "3") (pinfunction "D_3") (pintype "passive"))
    )
    (net (code "45") (name "Net-(T6-D)") (class "Default")
      (node (ref "R44") (pin "1") (pinfunction "1_1") (pintype "passive"))
      (node (ref "T6") (pin "3") (pinfunction "D_3") (pintype "passive"))
      (node (ref "T9") (pin "1") (pinfunction "G_1") (pintype "passive"))
    )
    (net (code "46") (name "Net-(T9-D)") (class "Default")
      (node (ref "D28") (pin "A") (pinfunction "A_A") (pintype "passive"))
      (node (ref "T9") (pin "3") (pinfunction "D_3") (pintype "passive"))
    )
    (net (code "47") (name "Net-(U9-ADJ)") (class "Default")
      (node (ref "R10") (pin "1") (pinfunction "1_1") (pintype "passive"))
      (node (ref "R30") (pin "2") (pinfunction "2_2") (pintype "passive"))
      (node (ref "U9") (pin "1") (pinfunction "ADJ_1") (pintype "input"))
    )
    (net (code "48") (name "Net-(U10-LOAD)") (class "Default")
      (node (ref "R40") (pin "1") (pinfunction "1_1") (pintype "passive"))
      (node (ref "U10") (pin "6") (pinfunction "LOAD_6") (pintype "output"))
    )
    (net (code "49") (name "PWM_RX") (class "Default")
      (node (ref "IC2") (pin "1") (pinfunction "OUT_1") (pintype "open_collector"))
      (node (ref "J6") (pin "9") (pinfunction "9_9") (pintype "passive"))
      (node (ref "R28") (pin "1") (pinfunction "1_1") (pintype "passive"))
    )
    (net (code "50") (name "PWM{slash}~{VPW}") (class "Default")
      (node (ref "J6") (pin "7") (pinfunction "7_7") (pintype "passive"))
      (node (ref "R32") (pin "1") (pinfunction "1_1") (pintype "passive"))
      (node (ref "T3") (pin "1") (pinfunction "G_1") (pintype "passive"))
    )
    (net (code "51") (name "SW_CAN") (class "Default")
      (node (ref "C6") (pin "1") (pinfunction "1_1") (pintype "passive"))
      (node (ref "D1") (pin "1") (pinfunction "A1_1") (pintype "passive"))
      (node (ref "J2") (pin "1") (pinfunction "1_1") (pintype "passive"))
      (node (ref "R13") (pin "2") (pinfunction "2_2") (pintype "passive"))
      (node (ref "R40") (pin "2") (pinfunction "2_2") (pintype "passive"))
      (node (ref "U10") (pin "7") (pinfunction "CANH_7") (pintype "bidirectional"))
    )
    (net (code "52") (name "SW_CAN_LOAD") (class "Default")
      (node (ref "J5") (pin "12") (pinfunction "12_12") (pintype "passive"))
      (node (ref "R21") (pin "1") (pinfunction "1_1") (pintype "passive"))
      (node (ref "T1") (pin "1") (pinfunction "G_1") (pintype "passive"))
    )
    (net (code "53") (name "SW_CAN_MODE0") (class "Default")
      (node (ref "J5") (pin "10") (pinfunction "10_10") (pintype "passive"))
      (node (ref "U10") (pin "2") (pinfunction "MODE0_2") (pintype "input"))
    )
    (net (code "54") (name "SW_CAN_MODE1") (class "Default")
      (node (ref "J5") (pin "11") (pinfunction "11_11") (pintype "passive"))
      (node (ref "U10") (pin "3") (pinfunction "MODE1_3") (pintype "input"))
    )
    (net (code "55") (name "SW_CAN_RX") (class "Default")
      (node (ref "J5") (pin "8") (pinfunction "8_8") (pintype "passive"))
      (node (ref "R12") (pin "1") (pinfunction "1_1") (pintype "passive"))
      (node (ref "U10") (pin "4") (pinfunction "RX_4") (pintype "input"))
    )
    (net (code "56") (name "SW_CAN_TX") (class "Default")
      (node (ref "J5") (pin "9") (pinfunction "9_9") (pintype "passive"))
      (node (ref "R46") (pin "1") (pinfunction "1_1") (pintype "passive"))
      (node (ref "U10") (pin "1") (pinfunction "TX_1") (pintype "input"))
    )
    (net (code "57") (name "UART_RX") (class "Default")
      (node (ref "CP1202N") (pin "18") (pinfunction "TXD_18") (pintype "output"))
      (node (ref "J5") (pin "1") (pinfunction "1_1") (pintype "passive"))
    )
    (net (code "58") (name "UART_TX") (class "Default")
      (node (ref "CP1202N") (pin "17") (pinfunction "RXD_17") (pintype "input"))
      (node (ref "J5") (pin "2") (pinfunction "2_2") (pintype "passive"))
    )
    (net (code "59") (name "VDD_CP") (class "Default")
      (node (ref "C4") (pin "1") (pinfunction "1_1") (pintype "passive"))
      (node (ref "C8") (pin "1") (pinfunction "1_1") (pintype "passive"))
      (node (ref "CP1202N") (pin "6") (pinfunction "VDD_6") (pintype "power_in"))
      (node (ref "R6") (pin "1") (pinfunction "1_1") (pintype "passive"))
      (node (ref "R8") (pin "2") (pinfunction "2_2") (pintype "passive"))
      (node (ref "R9") (pin "2") (pinfunction "2_2") (pintype "passive"))
    )
    (net (code "60") (name "VPW_RX") (class "Default")
      (node (ref "IC2") (pin "2") (pinfunction "OUT_2") (pintype "open_collector"))
      (node (ref "J6") (pin "8") (pinfunction "8_8") (pintype "passive"))
      (node (ref "R27") (pin "1") (pinfunction "1_1") (pintype "passive"))
    )
    (net (code "61") (name "V_J1850") (class "Default")
      (node (ref "R10") (pin "2") (pinfunction "2_2") (pintype "passive"))
      (node (ref "R44") (pin "2") (pinfunction "2_2") (pintype "passive"))
      (node (ref "T9") (pin "2") (pinfunction "S_2") (pintype "passive"))
      (node (ref "U9") (pin "2") (pinfunction "OUT_2") (pintype "output"))
      (node (ref "U9") (pin "4") (pinfunction "OUT_4") (pintype "output"))
    )
    (net (code "62") (name "unconnected-(CP1202N-CTS-Pad15)") (class "Default")
      (node (ref "CP1202N") (pin "15") (pinfunction "CTS_15") (pintype "input"))
    )
    (net (code "63") (name "unconnected-(CP1202N-GPIO0{slash}CLK-Pad2)") (class "Default")
      (node (ref "CP1202N") (pin "2") (pinfunction "GPIO0/CLK_2") (pintype "bidirectional"))
    )
    (net (code "64") (name "unconnected-(CP1202N-GPIO1{slash}RS485-Pad1)") (class "Default")
      (node (ref "CP1202N") (pin "1") (pinfunction "GPIO1/RS485_1") (pintype "bidirectional"))
    )
    (net (code "65") (name "unconnected-(CP1202N-NC-Pad10)") (class "Default")
      (node (ref "CP1202N") (pin "10") (pinfunction "NC_10") (pintype "bidirectional"))
    )
    (net (code "66") (name "unconnected-(CP1202N-RTS-Pad16)") (class "Default")
      (node (ref "CP1202N") (pin "16") (pinfunction "RTS_16") (pintype "output"))
    )
    (net (code "67") (name "unconnected-(CP1202N-SUSPEND-Pad14)") (class "Default")
      (node (ref "CP1202N") (pin "14") (pinfunction "SUSPEND_14") (pintype "output"))
    )
    (net (code "68") (name "unconnected-(CP1202N-SUSPENDB-Pad11)") (class "Default")
      (node (ref "CP1202N") (pin "11") (pinfunction "SUSPENDB_11") (pintype "output"))
    )
    (net (code "69") (name "unconnected-(CP1202N-WAKEUP-Pad13)") (class "Default")
      (node (ref "CP1202N") (pin "13") (pinfunction "WAKEUP_13") (pintype "input"))
    )
    (net (code "70") (name "unconnected-(D1-C-Pad3)") (class "Default")
      (node (ref "D1") (pin "3") (pinfunction "C_3") (pintype "passive"))
    )
    (net (code "71") (name "unconnected-(J5-Pad3)") (class "Default")
      (node (ref "J5") (pin "3") (pinfunction "3_3") (pintype "passive"))
    )
    (net (code "72") (name "~{ISO_K_TX}") (class "Default")
      (node (ref "J6") (pin "4") (pinfunction "4_4") (pintype "passive"))
      (node (ref "R11") (pin "1") (pinfunction "1_1") (pintype "passive"))
    )
    (net (code "73") (name "~{ISO_L_TX}") (class "Default")
      (node (ref "J6") (pin "5") (pinfunction "5_5") (pintype "passive"))
      (node (ref "R35") (pin "1") (pinfunction "1_1") (pintype "passive"))
    )
    (net (code "74") (name "~{ISO_RX}") (class "Default")
      (node (ref "IC2") (pin "14") (pinfunction "OUT_14") (pintype "open_collector"))
      (node (ref "J6") (pin "3") (pinfunction "3_3") (pintype "passive"))
      (node (ref "R43") (pin "1") (pinfunction "1_1") (pintype "passive"))
    )
    (net (code "75") (name "~{J1850_BUS-_TX}") (class "Default")
      (node (ref "J6") (pin "11") (pinfunction "11_11") (pintype "passive"))
      (node (ref "R38") (pin "2") (pinfunction "2_2") (pintype "passive"))
      (node (ref "T2") (pin "1") (pinfunction "G_1") (pintype "passive"))
    )
  )
)
